# MaTouch_ESP32-S3_7_5_Eink_AI_Mic_Array_V.net
KiCad netlist of a schematic drawn in EAGLE
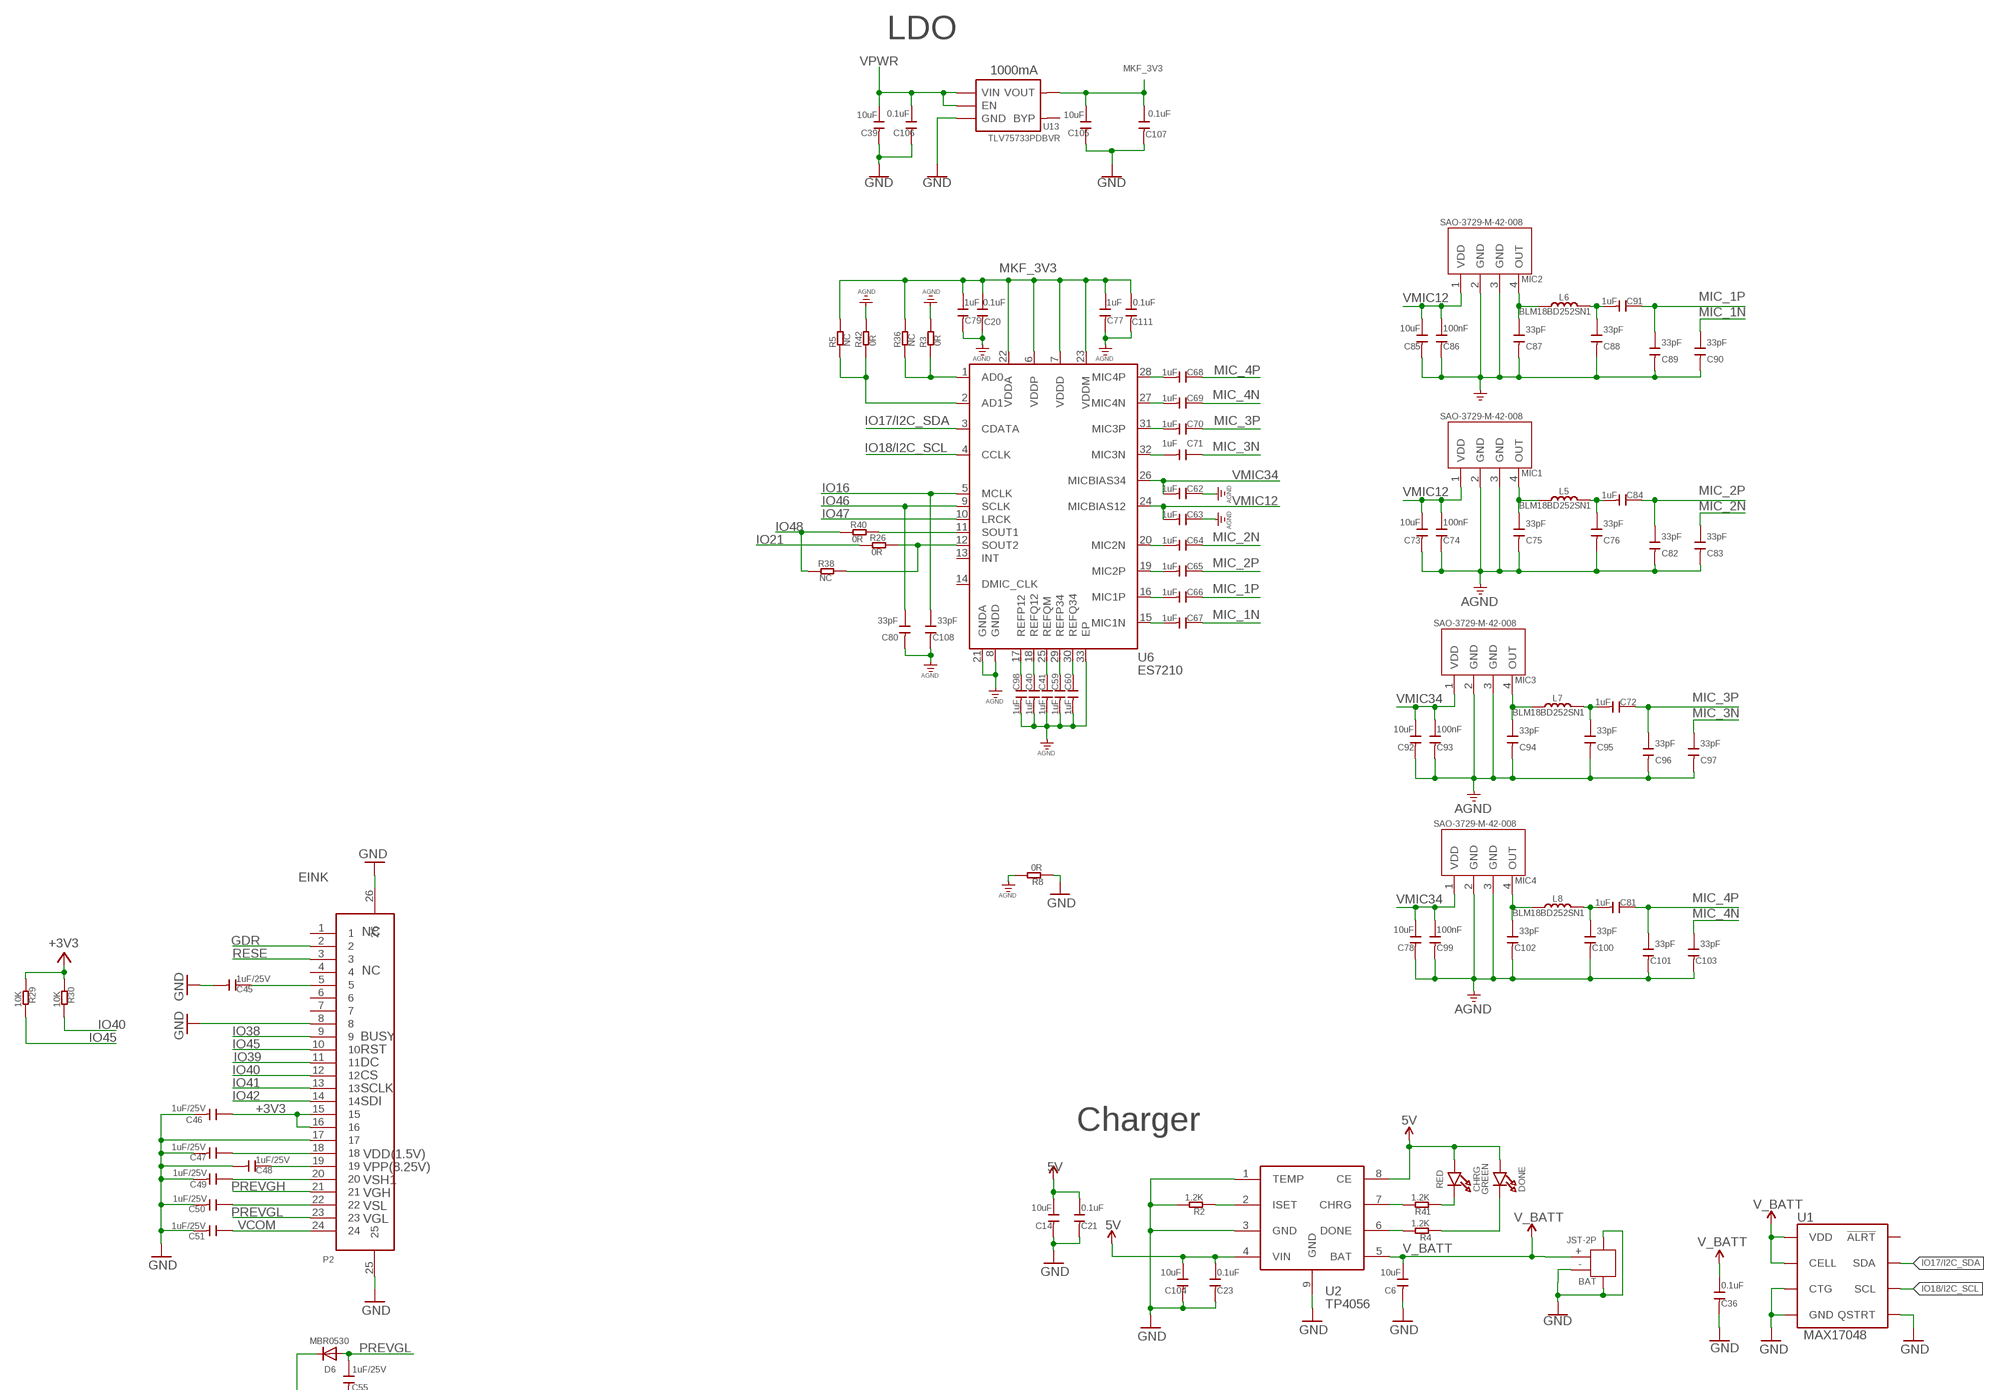
[diagram p0: schematic, sheet 1, part 1 of 3]
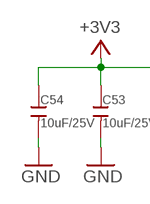
[diagram p1: schematic, sheet 1, part 2 of 3]
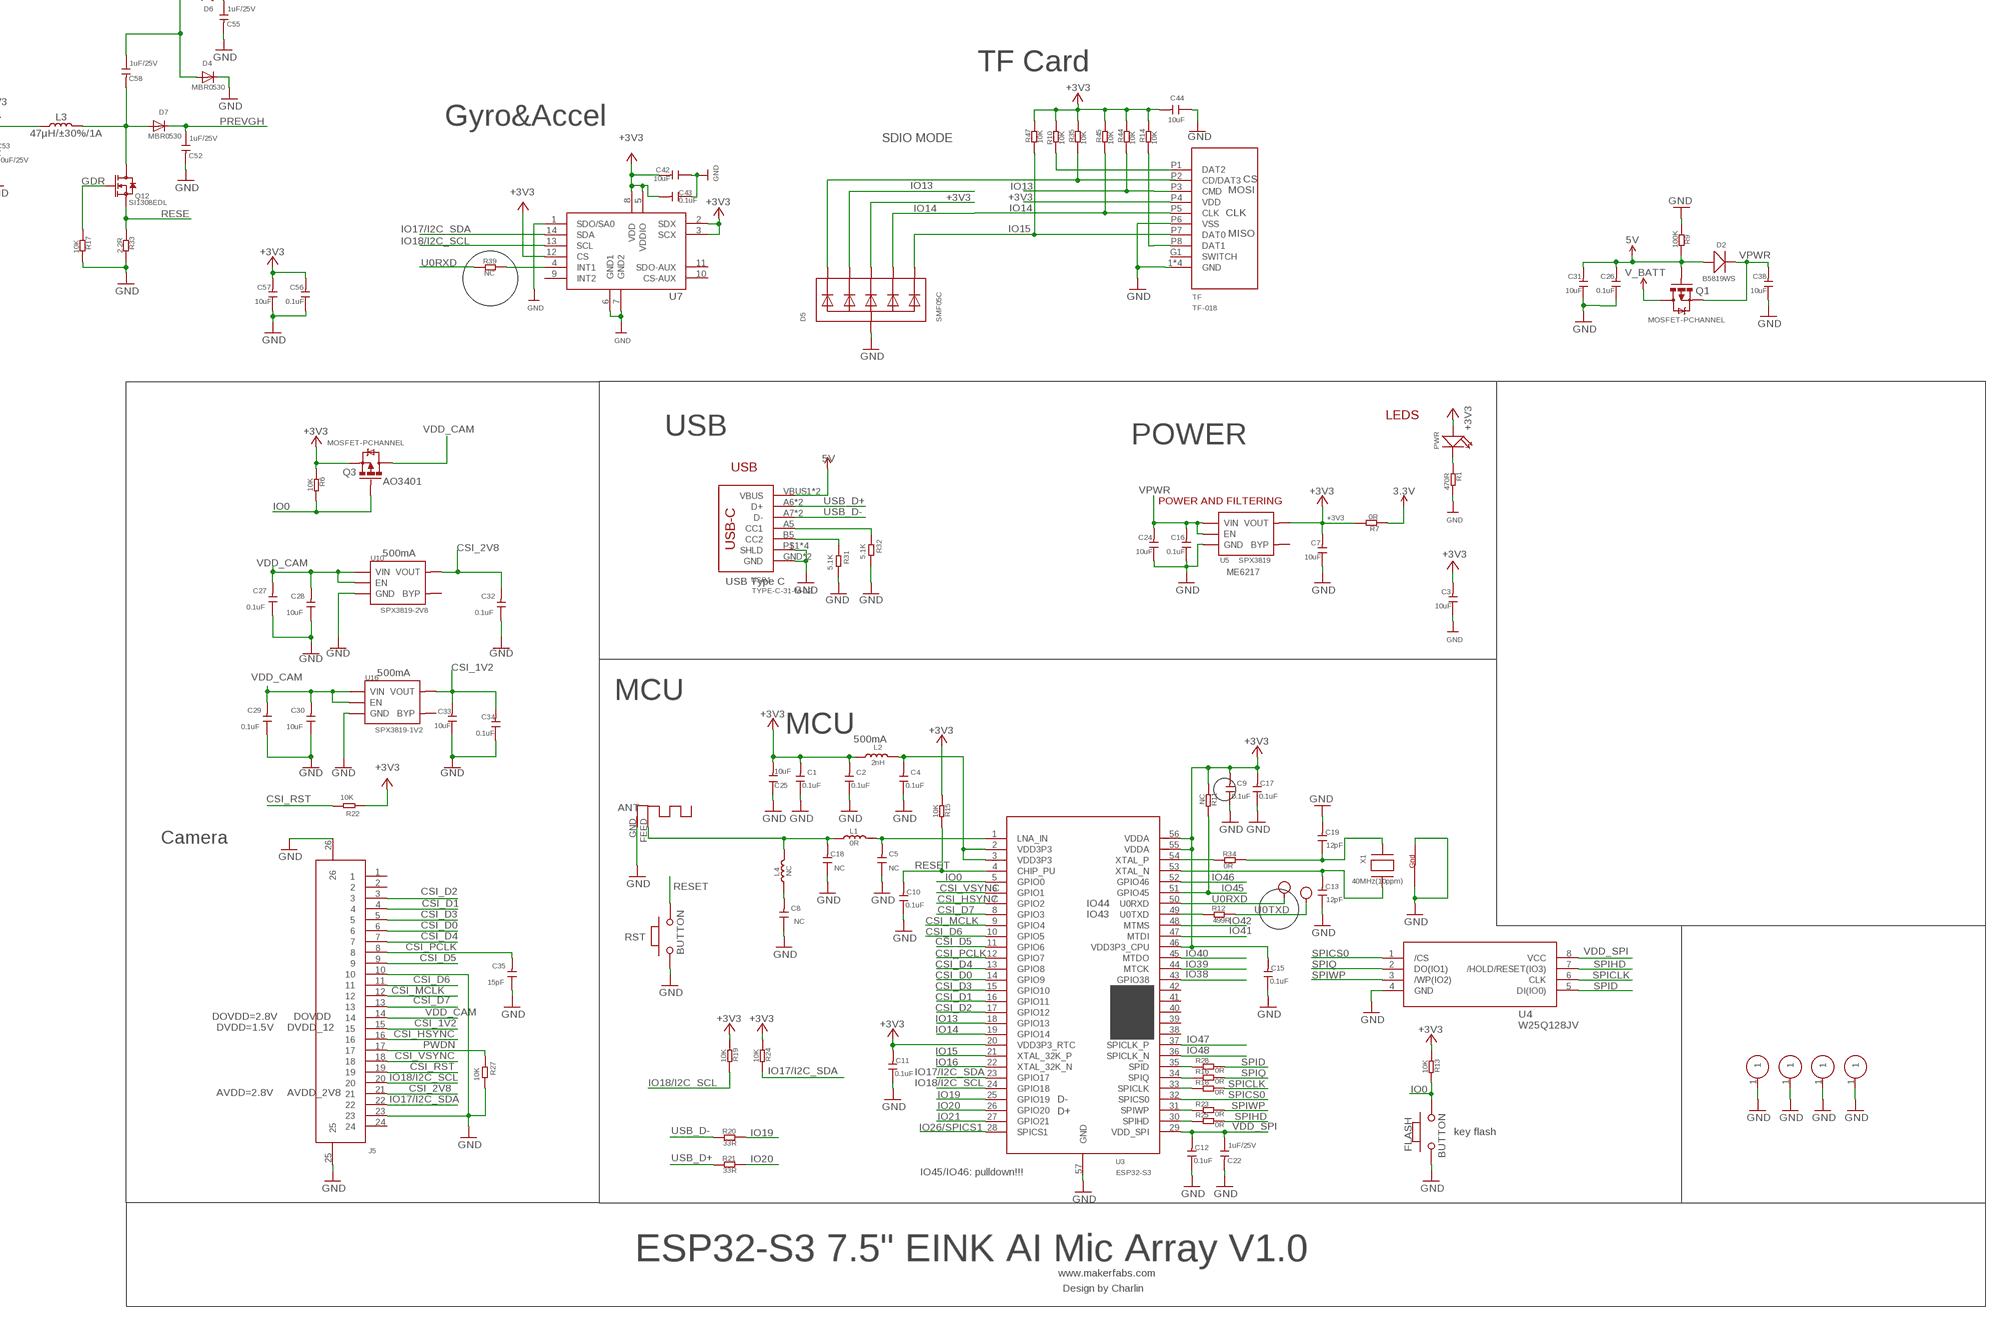
[diagram p2: schematic, sheet 1, part 3 of 3]

(export (version "E")
  (design (tool "Eeschema 10.0.6"))
  (components
    (comp (ref "ANT1")
      (value "ANTENNA")
      (footprint "eagle-import:RN-ANT")
      (libsource (lib "eagle-import") (part "ANTENNA"))
    )
    (comp (ref "BAT")
      (value "JST-2P")
      (footprint "eagle-import:HW2-SMD-2.0-90D")
      (libsource (lib "eagle-import") (part "JST-2P-SMD'2.0'"))
    )
    (comp (ref "C1")
      (value "0.1uF")
      (footprint "eagle-import:DISCRETE_C0402")
      (libsource (lib "eagle-import") (part "DISCRETE_C-0402"))
    )
    (comp (ref "C2")
      (value "0.1uF")
      (footprint "eagle-import:DISCRETE_C0402")
      (libsource (lib "eagle-import") (part "DISCRETE_C-0402"))
    )
    (comp (ref "C3")
      (value "10uF")
      (footprint "eagle-import:DISCRETE_C0402")
      (libsource (lib "eagle-import") (part "DISCRETE_C-0402"))
    )
    (comp (ref "C4")
      (value "0.1uF")
      (footprint "eagle-import:DISCRETE_C0402")
      (libsource (lib "eagle-import") (part "DISCRETE_C-0402"))
    )
    (comp (ref "C5")
      (value "NC")
      (footprint "eagle-import:DISCRETE_C0402")
      (libsource (lib "eagle-import") (part "DISCRETE_C-0402"))
    )
    (comp (ref "C6")
      (value "10uF")
      (footprint "eagle-import:DISCRETE_C0402")
      (libsource (lib "eagle-import") (part "DISCRETE_C-0402"))
    )
    (comp (ref "C7")
      (value "10uF")
      (footprint "eagle-import:DISCRETE_C0402")
      (libsource (lib "eagle-import") (part "DISCRETE_C-0402"))
    )
    (comp (ref "C8")
      (value "NC")
      (footprint "eagle-import:DISCRETE_C0402")
      (libsource (lib "eagle-import") (part "DISCRETE_C-0402"))
    )
    (comp (ref "C9")
      (value "0.1uF")
      (footprint "eagle-import:DISCRETE_C0402")
      (libsource (lib "eagle-import") (part "DISCRETE_C-0402"))
    )
    (comp (ref "C10")
      (value "0.1uF")
      (footprint "eagle-import:DISCRETE_C0402")
      (libsource (lib "eagle-import") (part "DISCRETE_C-0402"))
    )
    (comp (ref "C11")
      (value "0.1uF")
      (footprint "eagle-import:DISCRETE_C0402")
      (libsource (lib "eagle-import") (part "DISCRETE_C-0402"))
    )
    (comp (ref "C12")
      (value "0.1uF")
      (footprint "eagle-import:DISCRETE_C0402")
      (libsource (lib "eagle-import") (part "DISCRETE_C-0402"))
    )
    (comp (ref "C13")
      (value "12pF")
      (footprint "eagle-import:DISCRETE_C0402")
      (libsource (lib "eagle-import") (part "DISCRETE_C-0402"))
    )
    (comp (ref "C14")
      (value "10uF")
      (footprint "eagle-import:DISCRETE_C0402")
      (libsource (lib "eagle-import") (part "DISCRETE_C-0402"))
    )
    (comp (ref "C15")
      (value "0.1uF")
      (footprint "eagle-import:DISCRETE_C0402")
      (libsource (lib "eagle-import") (part "DISCRETE_C-0402"))
    )
    (comp (ref "C16")
      (value "0.1uF")
      (footprint "eagle-import:DISCRETE_C0402")
      (libsource (lib "eagle-import") (part "DISCRETE_C-0402"))
    )
    (comp (ref "C17")
      (value "0.1uF")
      (footprint "eagle-import:DISCRETE_C0402")
      (libsource (lib "eagle-import") (part "DISCRETE_C-0402"))
    )
    (comp (ref "C18")
      (value "NC")
      (footprint "eagle-import:DISCRETE_C0402")
      (libsource (lib "eagle-import") (part "DISCRETE_C-0402"))
    )
    (comp (ref "C19")
      (value "12pF")
      (footprint "eagle-import:DISCRETE_C0402")
      (libsource (lib "eagle-import") (part "DISCRETE_C-0402"))
    )
    (comp (ref "C20")
      (value "0.1uF")
      (footprint "eagle-import:DISCRETE_C0402")
      (libsource (lib "eagle-import") (part "DISCRETE_C-0402"))
    )
    (comp (ref "C21")
      (value "0.1uF")
      (footprint "eagle-import:DISCRETE_C0402")
      (libsource (lib "eagle-import") (part "DISCRETE_C-0402"))
    )
    (comp (ref "C22")
      (value "1uF/25V")
      (footprint "eagle-import:DISCRETE_C0402")
      (libsource (lib "eagle-import") (part "DISCRETE_C-0402"))
    )
    (comp (ref "C23")
      (value "0.1uF")
      (footprint "eagle-import:DISCRETE_C0402")
      (libsource (lib "eagle-import") (part "DISCRETE_C-0402"))
    )
    (comp (ref "C24")
      (value "10uF")
      (footprint "eagle-import:DISCRETE_C0402")
      (libsource (lib "eagle-import") (part "DISCRETE_C-0402"))
    )
    (comp (ref "C25")
      (value "10uF")
      (footprint "eagle-import:DISCRETE_C0603")
      (libsource (lib "eagle-import") (part "DISCRETE_C-0603"))
    )
    (comp (ref "C26")
      (value "0.1uF")
      (footprint "eagle-import:DISCRETE_C0402")
      (libsource (lib "eagle-import") (part "DISCRETE_C-0402"))
    )
    (comp (ref "C27")
      (value "0.1uF")
      (footprint "eagle-import:DISCRETE_C0402")
      (libsource (lib "eagle-import") (part "DISCRETE_C-0402"))
    )
    (comp (ref "C28")
      (value "10uF")
      (footprint "eagle-import:DISCRETE_C0402")
      (libsource (lib "eagle-import") (part "DISCRETE_C-0402"))
    )
    (comp (ref "C29")
      (value "0.1uF")
      (footprint "eagle-import:DISCRETE_C0402")
      (libsource (lib "eagle-import") (part "DISCRETE_C-0402"))
    )
    (comp (ref "C30")
      (value "10uF")
      (footprint "eagle-import:DISCRETE_C0402")
      (libsource (lib "eagle-import") (part "DISCRETE_C-0402"))
    )
    (comp (ref "C31")
      (value "10uF")
      (footprint "eagle-import:DISCRETE_C0402")
      (libsource (lib "eagle-import") (part "DISCRETE_C-0402"))
    )
    (comp (ref "C32")
      (value "0.1uF")
      (footprint "eagle-import:DISCRETE_C0402")
      (libsource (lib "eagle-import") (part "DISCRETE_C-0402"))
    )
    (comp (ref "C33")
      (value "10uF")
      (footprint "eagle-import:DISCRETE_C0402")
      (libsource (lib "eagle-import") (part "DISCRETE_C-0402"))
    )
    (comp (ref "C34")
      (value "0.1uF")
      (footprint "eagle-import:DISCRETE_C0402")
      (libsource (lib "eagle-import") (part "DISCRETE_C-0402"))
    )
    (comp (ref "C35")
      (value "15pF")
      (footprint "eagle-import:DISCRETE_C0402")
      (libsource (lib "eagle-import") (part "DISCRETE_C-0402"))
    )
    (comp (ref "C36")
      (value "0.1uF")
      (footprint "eagle-import:DISCRETE_C0402")
      (libsource (lib "eagle-import") (part "DISCRETE_C-0402"))
    )
    (comp (ref "C38")
      (value "10uF")
      (footprint "eagle-import:DISCRETE_C0402")
      (libsource (lib "eagle-import") (part "DISCRETE_C-0402"))
    )
    (comp (ref "C39")
      (value "10uF")
      (footprint "eagle-import:DISCRETE_C0402")
      (libsource (lib "eagle-import") (part "DISCRETE_C-0402"))
    )
    (comp (ref "C40")
      (value "1uF")
      (footprint "eagle-import:DISCRETE_C0402")
      (libsource (lib "eagle-import") (part "DISCRETE_C-0402"))
    )
    (comp (ref "C41")
      (value "1uF")
      (footprint "eagle-import:DISCRETE_C0402")
      (libsource (lib "eagle-import") (part "DISCRETE_C-0402"))
    )
    (comp (ref "C42")
      (value "10uF")
      (footprint "eagle-import:DISCRETE_C0402")
      (libsource (lib "eagle-import") (part "DISCRETE_C-0402"))
    )
    (comp (ref "C43")
      (value "0.1uF")
      (footprint "eagle-import:DISCRETE_C0402")
      (libsource (lib "eagle-import") (part "DISCRETE_C-0402"))
    )
    (comp (ref "C44")
      (value "10uF")
      (footprint "eagle-import:DISCRETE_C0402")
      (libsource (lib "eagle-import") (part "DISCRETE_C-0402"))
    )
    (comp (ref "C45")
      (value "1uF/25V")
      (footprint "eagle-import:DISCRETE_C0402")
      (libsource (lib "eagle-import") (part "DISCRETE_C-0402"))
    )
    (comp (ref "C46")
      (value "1uF/25V")
      (footprint "eagle-import:DISCRETE_C0402")
      (libsource (lib "eagle-import") (part "DISCRETE_C-0402"))
    )
    (comp (ref "C47")
      (value "1uF/25V")
      (footprint "eagle-import:DISCRETE_C0402")
      (libsource (lib "eagle-import") (part "DISCRETE_C-0402"))
    )
    (comp (ref "C48")
      (value "1uF/25V")
      (footprint "eagle-import:DISCRETE_C0402")
      (libsource (lib "eagle-import") (part "DISCRETE_C-0402"))
    )
    (comp (ref "C49")
      (value "1uF/25V")
      (footprint "eagle-import:DISCRETE_C0402")
      (libsource (lib "eagle-import") (part "DISCRETE_C-0402"))
    )
    (comp (ref "C50")
      (value "1uF/25V")
      (footprint "eagle-import:DISCRETE_C0402")
      (libsource (lib "eagle-import") (part "DISCRETE_C-0402"))
    )
    (comp (ref "C51")
      (value "1uF/25V")
      (footprint "eagle-import:DISCRETE_C0402")
      (libsource (lib "eagle-import") (part "DISCRETE_C-0402"))
    )
    (comp (ref "C52")
      (value "1uF/25V")
      (footprint "eagle-import:DISCRETE_C0402")
      (libsource (lib "eagle-import") (part "DISCRETE_C-0402"))
    )
    (comp (ref "C53")
      (value "10uF/25V")
      (footprint "eagle-import:C0603")
      (libsource (lib "eagle-import") (part "C-0603"))
    )
    (comp (ref "C54")
      (value "10uF/25V")
      (footprint "eagle-import:C0603")
      (libsource (lib "eagle-import") (part "C-0603"))
    )
    (comp (ref "C55")
      (value "1uF/25V")
      (footprint "eagle-import:DISCRETE_C0402")
      (libsource (lib "eagle-import") (part "DISCRETE_C-0402"))
    )
    (comp (ref "C56")
      (value "0.1uF")
      (footprint "eagle-import:DISCRETE_C0402")
      (libsource (lib "eagle-import") (part "DISCRETE_C-0402"))
    )
    (comp (ref "C57")
      (value "10uF")
      (footprint "eagle-import:DISCRETE_C0402")
      (libsource (lib "eagle-import") (part "DISCRETE_C-0402"))
    )
    (comp (ref "C58")
      (value "1uF/25V")
      (footprint "eagle-import:DISCRETE_C0402")
      (libsource (lib "eagle-import") (part "DISCRETE_C-0402"))
    )
    (comp (ref "C59")
      (value "1uF")
      (footprint "eagle-import:DISCRETE_C0402")
      (libsource (lib "eagle-import") (part "DISCRETE_C-0402"))
    )
    (comp (ref "C60")
      (value "1uF")
      (footprint "eagle-import:DISCRETE_C0402")
      (libsource (lib "eagle-import") (part "DISCRETE_C-0402"))
    )
    (comp (ref "C62")
      (value "1uF")
      (footprint "eagle-import:DISCRETE_C0402")
      (libsource (lib "eagle-import") (part "DISCRETE_C-0402"))
    )
    (comp (ref "C63")
      (value "1uF")
      (footprint "eagle-import:DISCRETE_C0402")
      (libsource (lib "eagle-import") (part "DISCRETE_C-0402"))
    )
    (comp (ref "C64")
      (value "1uF")
      (footprint "eagle-import:DISCRETE_C0402")
      (libsource (lib "eagle-import") (part "DISCRETE_C-0402"))
    )
    (comp (ref "C65")
      (value "1uF")
      (footprint "eagle-import:DISCRETE_C0402")
      (libsource (lib "eagle-import") (part "DISCRETE_C-0402"))
    )
    (comp (ref "C66")
      (value "1uF")
      (footprint "eagle-import:DISCRETE_C0402")
      (libsource (lib "eagle-import") (part "DISCRETE_C-0402"))
    )
    (comp (ref "C67")
      (value "1uF")
      (footprint "eagle-import:DISCRETE_C0402")
      (libsource (lib "eagle-import") (part "DISCRETE_C-0402"))
    )
    (comp (ref "C68")
      (value "1uF")
      (footprint "eagle-import:DISCRETE_C0402")
      (libsource (lib "eagle-import") (part "DISCRETE_C-0402"))
    )
    (comp (ref "C69")
      (value "1uF")
      (footprint "eagle-import:DISCRETE_C0402")
      (libsource (lib "eagle-import") (part "DISCRETE_C-0402"))
    )
    (comp (ref "C70")
      (value "1uF")
      (footprint "eagle-import:DISCRETE_C0402")
      (libsource (lib "eagle-import") (part "DISCRETE_C-0402"))
    )
    (comp (ref "C71")
      (value "1uF")
      (footprint "eagle-import:DISCRETE_C0402")
      (libsource (lib "eagle-import") (part "DISCRETE_C-0402"))
    )
    (comp (ref "C72")
      (value "1uF")
      (footprint "eagle-import:DISCRETE_C0402")
      (libsource (lib "eagle-import") (part "DISCRETE_C-0402"))
    )
    (comp (ref "C73")
      (value "10uF")
      (footprint "eagle-import:DISCRETE_C0402")
      (libsource (lib "eagle-import") (part "DISCRETE_C-0402"))
    )
    (comp (ref "C74")
      (value "100nF")
      (footprint "eagle-import:DISCRETE_C0402")
      (libsource (lib "eagle-import") (part "DISCRETE_C-0402"))
    )
    (comp (ref "C75")
      (value "33pF")
      (footprint "eagle-import:DISCRETE_C0402")
      (libsource (lib "eagle-import") (part "DISCRETE_C-0402"))
    )
    (comp (ref "C76")
      (value "33pF")
      (footprint "eagle-import:DISCRETE_C0402")
      (libsource (lib "eagle-import") (part "DISCRETE_C-0402"))
    )
    (comp (ref "C77")
      (value "1uF")
      (footprint "eagle-import:DISCRETE_C0402")
      (libsource (lib "eagle-import") (part "DISCRETE_C-0402"))
    )
    (comp (ref "C78")
      (value "10uF")
      (footprint "eagle-import:DISCRETE_C0402")
      (libsource (lib "eagle-import") (part "DISCRETE_C-0402"))
    )
    (comp (ref "C79")
      (value "1uF")
      (footprint "eagle-import:DISCRETE_C0402")
      (libsource (lib "eagle-import") (part "DISCRETE_C-0402"))
    )
    (comp (ref "C80")
      (value "33pF")
      (footprint "eagle-import:DISCRETE_C0402")
      (libsource (lib "eagle-import") (part "DISCRETE_C-0402"))
    )
    (comp (ref "C81")
      (value "1uF")
      (footprint "eagle-import:DISCRETE_C0402")
      (libsource (lib "eagle-import") (part "DISCRETE_C-0402"))
    )
    (comp (ref "C82")
      (value "33pF")
      (footprint "eagle-import:DISCRETE_C0402")
      (libsource (lib "eagle-import") (part "DISCRETE_C-0402"))
    )
    (comp (ref "C83")
      (value "33pF")
      (footprint "eagle-import:DISCRETE_C0402")
      (libsource (lib "eagle-import") (part "DISCRETE_C-0402"))
    )
    (comp (ref "C84")
      (value "1uF")
      (footprint "eagle-import:DISCRETE_C0402")
      (libsource (lib "eagle-import") (part "DISCRETE_C-0402"))
    )
    (comp (ref "C85")
      (value "10uF")
      (footprint "eagle-import:DISCRETE_C0402")
      (libsource (lib "eagle-import") (part "DISCRETE_C-0402"))
    )
    (comp (ref "C86")
      (value "100nF")
      (footprint "eagle-import:DISCRETE_C0402")
      (libsource (lib "eagle-import") (part "DISCRETE_C-0402"))
    )
    (comp (ref "C87")
      (value "33pF")
      (footprint "eagle-import:DISCRETE_C0402")
      (libsource (lib "eagle-import") (part "DISCRETE_C-0402"))
    )
    (comp (ref "C88")
      (value "33pF")
      (footprint "eagle-import:DISCRETE_C0402")
      (libsource (lib "eagle-import") (part "DISCRETE_C-0402"))
    )
    (comp (ref "C89")
      (value "33pF")
      (footprint "eagle-import:DISCRETE_C0402")
      (libsource (lib "eagle-import") (part "DISCRETE_C-0402"))
    )
    (comp (ref "C90")
      (value "33pF")
      (footprint "eagle-import:DISCRETE_C0402")
      (libsource (lib "eagle-import") (part "DISCRETE_C-0402"))
    )
    (comp (ref "C91")
      (value "1uF")
      (footprint "eagle-import:DISCRETE_C0402")
      (libsource (lib "eagle-import") (part "DISCRETE_C-0402"))
    )
    (comp (ref "C92")
      (value "10uF")
      (footprint "eagle-import:DISCRETE_C0402")
      (libsource (lib "eagle-import") (part "DISCRETE_C-0402"))
    )
    (comp (ref "C93")
      (value "100nF")
      (footprint "eagle-import:DISCRETE_C0402")
      (libsource (lib "eagle-import") (part "DISCRETE_C-0402"))
    )
    (comp (ref "C94")
      (value "33pF")
      (footprint "eagle-import:DISCRETE_C0402")
      (libsource (lib "eagle-import") (part "DISCRETE_C-0402"))
    )
    (comp (ref "C95")
      (value "33pF")
      (footprint "eagle-import:DISCRETE_C0402")
      (libsource (lib "eagle-import") (part "DISCRETE_C-0402"))
    )
    (comp (ref "C96")
      (value "33pF")
      (footprint "eagle-import:DISCRETE_C0402")
      (libsource (lib "eagle-import") (part "DISCRETE_C-0402"))
    )
    (comp (ref "C97")
      (value "33pF")
      (footprint "eagle-import:DISCRETE_C0402")
      (libsource (lib "eagle-import") (part "DISCRETE_C-0402"))
    )
    (comp (ref "C98")
      (value "1uF")
      (footprint "eagle-import:DISCRETE_C0402")
      (libsource (lib "eagle-import") (part "DISCRETE_C-0402"))
    )
    (comp (ref "C99")
      (value "100nF")
      (footprint "eagle-import:DISCRETE_C0402")
      (libsource (lib "eagle-import") (part "DISCRETE_C-0402"))
    )
    (comp (ref "C100")
      (value "33pF")
      (footprint "eagle-import:DISCRETE_C0402")
      (libsource (lib "eagle-import") (part "DISCRETE_C-0402"))
    )
    (comp (ref "C101")
      (value "33pF")
      (footprint "eagle-import:DISCRETE_C0402")
      (libsource (lib "eagle-import") (part "DISCRETE_C-0402"))
    )
    (comp (ref "C102")
      (value "33pF")
      (footprint "eagle-import:DISCRETE_C0402")
      (libsource (lib "eagle-import") (part "DISCRETE_C-0402"))
    )
    (comp (ref "C103")
      (value "33pF")
      (footprint "eagle-import:DISCRETE_C0402")
      (libsource (lib "eagle-import") (part "DISCRETE_C-0402"))
    )
    (comp (ref "C104")
      (value "10uF")
      (footprint "eagle-import:DISCRETE_C0402")
      (libsource (lib "eagle-import") (part "DISCRETE_C-0402"))
    )
    (comp (ref "C105")
      (value "10uF")
      (footprint "eagle-import:DISCRETE_C0402")
      (libsource (lib "eagle-import") (part "DISCRETE_C-0402"))
    )
    (comp (ref "C106")
      (value "0.1uF")
      (footprint "eagle-import:DISCRETE_C0402")
      (libsource (lib "eagle-import") (part "DISCRETE_C-0402"))
    )
    (comp (ref "C107")
      (value "0.1uF")
      (footprint "eagle-import:DISCRETE_C0402")
      (libsource (lib "eagle-import") (part "DISCRETE_C-0402"))
    )
    (comp (ref "C108")
      (value "33pF")
      (footprint "eagle-import:DISCRETE_C0402")
      (libsource (lib "eagle-import") (part "DISCRETE_C-0402"))
    )
    (comp (ref "C111")
      (value "0.1uF")
      (footprint "eagle-import:DISCRETE_C0402")
      (libsource (lib "eagle-import") (part "DISCRETE_C-0402"))
    )
    (comp (ref "CHRG")
      (value "RED")
      (footprint "eagle-import:CHIPLED_0805_NOOUTLINE")
      (libsource (lib "eagle-import") (part "LED0805_NOOUTLINE"))
    )
    (comp (ref "D2")
      (value "B5819WS")
      (footprint "eagle-import:SOD323")
      (libsource (lib "eagle-import") (part "D'0805'"))
    )
    (comp (ref "D4")
      (value "MBR0530")
      (footprint "eagle-import:SOD-323F")
      (libsource (lib "eagle-import") (part "DIODESOD-323F"))
    )
    (comp (ref "D5")
      (value "SMF05C")
      (footprint "eagle-import:SOT363")
      (libsource (lib "eagle-import") (part "TVSARRAY_5LANE"))
    )
    (comp (ref "D6")
      (value "MBR0530")
      (footprint "eagle-import:SOD-323F")
      (libsource (lib "eagle-import") (part "DIODESOD-323F"))
    )
    (comp (ref "D7")
      (value "MBR0530")
      (footprint "eagle-import:SOD-323F")
      (libsource (lib "eagle-import") (part "DIODESOD-323F"))
    )
    (comp (ref "DONE")
      (value "GREEN")
      (footprint "eagle-import:CHIPLED_0805_NOOUTLINE")
      (libsource (lib "eagle-import") (part "LED0805_NOOUTLINE"))
    )
    (comp (ref "FLASH")
      (value "BUTTON")
      (footprint "eagle-import:157SW")
      (libsource (lib "eagle-import") (part "PB157"))
    )
    (comp (ref "J5")
      (value "FPC-24P")
      (footprint "eagle-import:SMD26-50P-1760L450W")
      (libsource (lib "eagle-import") (part "FPC-24P"))
    )
    (comp (ref "L1")
      (value "0R")
      (footprint "eagle-import:DISCRETE_L0402")
      (libsource (lib "eagle-import") (part "DISCRETE_L0402"))
    )
    (comp (ref "L2")
      (value "2nH")
      (footprint "eagle-import:DISCRETE_L0603")
      (libsource (lib "eagle-import") (part "DISCRETE_L0603"))
    )
    (comp (ref "L3")
      (value "47µH/±30%/1A")
      (footprint "eagle-import:CR54")
      (fields (field (name "PROD_ID") "NDUC-10789"))
      (libsource (lib "eagle-import") (part "INDUCTOR-CR54-47UH"))
    )
    (comp (ref "L4")
      (value "NC")
      (footprint "eagle-import:DISCRETE_L0402")
      (libsource (lib "eagle-import") (part "DISCRETE_L0402"))
    )
    (comp (ref "L5")
      (value "BLM18BD252SN1")
      (footprint "eagle-import:L0603")
      (libsource (lib "eagle-import") (part "INDUCTOR/FERRITE-BEAD'0603'"))
    )
    (comp (ref "L6")
      (value "BLM18BD252SN1")
      (footprint "eagle-import:L0603")
      (libsource (lib "eagle-import") (part "INDUCTOR/FERRITE-BEAD'0603'"))
    )
    (comp (ref "L7")
      (value "BLM18BD252SN1")
      (footprint "eagle-import:L0603")
      (libsource (lib "eagle-import") (part "INDUCTOR/FERRITE-BEAD'0603'"))
    )
    (comp (ref "L8")
      (value "BLM18BD252SN1")
      (footprint "eagle-import:L0603")
      (libsource (lib "eagle-import") (part "INDUCTOR/FERRITE-BEAD'0603'"))
    )
    (comp (ref "MIC1")
      (value "SAO-3729-M-42-008")
      (footprint "eagle-import:MIC4-SMD-3.76X2.95MM")
      (libsource (lib "eagle-import") (part "MIC-MSM421A3729H8-C"))
    )
    (comp (ref "MIC2")
      (value "SAO-3729-M-42-008")
      (footprint "eagle-import:MIC4-SMD-3.76X2.95MM")
      (libsource (lib "eagle-import") (part "MIC-MSM421A3729H8-C"))
    )
    (comp (ref "MIC3")
      (value "SAO-3729-M-42-008")
      (footprint "eagle-import:MIC4-SMD-3.76X2.95MM")
      (libsource (lib "eagle-import") (part "MIC-MSM421A3729H8-C"))
    )
    (comp (ref "MIC4")
      (value "SAO-3729-M-42-008")
      (footprint "eagle-import:MIC4-SMD-3.76X2.95MM")
      (libsource (lib "eagle-import") (part "MIC-MSM421A3729H8-C"))
    )
    (comp (ref "P2")
      (value "FPC-24P")
      (footprint "eagle-import:SMD26-50P-1760L450W")
      (libsource (lib "eagle-import") (part "FPC-24P"))
    )
    (comp (ref "PWR")
      (value "DISCRETE_LED0603")
      (footprint "eagle-import:DISCRETE_LED-0603")
      (libsource (lib "eagle-import") (part "DISCRETE_LED0603"))
    )
    (comp (ref "Q1")
      (value "MOSFET-PCHANNEL")
      (footprint "eagle-import:SOT23-3")
      (libsource (lib "eagle-import") (part "MOSFET-PCHANNEL"))
    )
    (comp (ref "Q3")
      (value "MOSFET-PCHANNEL")
      (footprint "eagle-import:SOT23-3")
      (libsource (lib "eagle-import") (part "MOSFET-PCHANNEL"))
    )
    (comp (ref "Q12")
      (value "SI1308EDL")
      (footprint "eagle-import:SOT23")
      (libsource (lib "eagle-import") (part "MOSFET-N'SOT23'"))
    )
    (comp (ref "R1")
      (value "470R")
      (footprint "eagle-import:DISCRETE_R0402")
      (libsource (lib "eagle-import") (part "DISCRETE_R-0402"))
    )
    (comp (ref "R2")
      (value "1.2K")
      (footprint "eagle-import:DISCRETE_R0402")
      (libsource (lib "eagle-import") (part "DISCRETE_R-0402"))
    )
    (comp (ref "R3")
      (value "0R")
      (footprint "eagle-import:DISCRETE_R0402")
      (libsource (lib "eagle-import") (part "DISCRETE_R-0402"))
    )
    (comp (ref "R4")
      (value "1.2K")
      (footprint "eagle-import:DISCRETE_R0402")
      (libsource (lib "eagle-import") (part "DISCRETE_R-0402"))
    )
    (comp (ref "R5")
      (value "NC")
      (footprint "eagle-import:DISCRETE_R0402")
      (libsource (lib "eagle-import") (part "DISCRETE_R-0402"))
    )
    (comp (ref "R6")
      (value "10K")
      (footprint "eagle-import:DISCRETE_R0402")
      (libsource (lib "eagle-import") (part "DISCRETE_R-0402"))
    )
    (comp (ref "R7")
      (value "0R")
      (footprint "eagle-import:DISCRETE_R0402")
      (libsource (lib "eagle-import") (part "DISCRETE_R-0402"))
    )
    (comp (ref "R8")
      (value "0R")
      (footprint "eagle-import:DISCRETE_R0402")
      (libsource (lib "eagle-import") (part "DISCRETE_R-0402"))
    )
    (comp (ref "R9")
      (value "100K")
      (footprint "eagle-import:DISCRETE_R0402")
      (libsource (lib "eagle-import") (part "DISCRETE_R-0402"))
    )
    (comp (ref "R10")
      (value "10K")
      (footprint "eagle-import:DISCRETE_R0402")
      (libsource (lib "eagle-import") (part "DISCRETE_R-0402"))
    )
    (comp (ref "R11")
      (value "NC")
      (footprint "eagle-import:DISCRETE_R0402")
      (libsource (lib "eagle-import") (part "DISCRETE_R-0402"))
    )
    (comp (ref "R12")
      (value "499R")
      (footprint "eagle-import:DISCRETE_R0402")
      (libsource (lib "eagle-import") (part "DISCRETE_R-0402"))
    )
    (comp (ref "R13")
      (value "10K")
      (footprint "eagle-import:DISCRETE_R0402")
      (libsource (lib "eagle-import") (part "DISCRETE_R-0402"))
    )
    (comp (ref "R14")
      (value "10K")
      (footprint "eagle-import:DISCRETE_R0402")
      (libsource (lib "eagle-import") (part "DISCRETE_R-0402"))
    )
    (comp (ref "R15")
      (value "10K")
      (footprint "eagle-import:DISCRETE_R0402")
      (libsource (lib "eagle-import") (part "DISCRETE_R-0402"))
    )
    (comp (ref "R16")
      (value "0R")
      (footprint "eagle-import:DISCRETE_R0402")
      (libsource (lib "eagle-import") (part "DISCRETE_R-0402"))
    )
    (comp (ref "R17")
      (value "10K")
      (footprint "eagle-import:DISCRETE_R0402")
      (libsource (lib "eagle-import") (part "DISCRETE_R-0402"))
    )
    (comp (ref "R18")
      (value "0R")
      (footprint "eagle-import:DISCRETE_R0402")
      (libsource (lib "eagle-import") (part "DISCRETE_R-0402"))
    )
    (comp (ref "R19")
      (value "10K")
      (footprint "eagle-import:DISCRETE_R0402")
      (libsource (lib "eagle-import") (part "DISCRETE_R-0402"))
    )
    (comp (ref "R20")
      (value "33R")
      (footprint "eagle-import:DISCRETE_R0402")
      (libsource (lib "eagle-import") (part "DISCRETE_R-0402"))
    )
    (comp (ref "R21")
      (value "33R")
      (footprint "eagle-import:DISCRETE_R0402")
      (libsource (lib "eagle-import") (part "DISCRETE_R-0402"))
    )
    (comp (ref "R22")
      (value "10K")
      (footprint "eagle-import:DISCRETE_R0402")
      (libsource (lib "eagle-import") (part "DISCRETE_R-0402"))
    )
    (comp (ref "R23")
      (value "0R")
      (footprint "eagle-import:DISCRETE_R0402")
      (libsource (lib "eagle-import") (part "DISCRETE_R-0402"))
    )
    (comp (ref "R24")
      (value "10K")
      (footprint "eagle-import:DISCRETE_R0402")
      (libsource (lib "eagle-import") (part "DISCRETE_R-0402"))
    )
    (comp (ref "R25")
      (value "0R")
      (footprint "eagle-import:DISCRETE_R0402")
      (libsource (lib "eagle-import") (part "DISCRETE_R-0402"))
    )
    (comp (ref "R26")
      (value "0R")
      (footprint "eagle-import:DISCRETE_R0402")
      (libsource (lib "eagle-import") (part "DISCRETE_R-0402"))
    )
    (comp (ref "R27")
      (value "10K")
      (footprint "eagle-import:DISCRETE_R0402")
      (libsource (lib "eagle-import") (part "DISCRETE_R-0402"))
    )
    (comp (ref "R28")
      (value "0R")
      (footprint "eagle-import:DISCRETE_R0402")
      (libsource (lib "eagle-import") (part "DISCRETE_R-0402"))
    )
    (comp (ref "R29")
      (value "10K")
      (footprint "eagle-import:DISCRETE_R0402")
      (libsource (lib "eagle-import") (part "DISCRETE_R-0402"))
    )
    (comp (ref "R30")
      (value "10K")
      (footprint "eagle-import:DISCRETE_R0402")
      (libsource (lib "eagle-import") (part "DISCRETE_R-0402"))
    )
    (comp (ref "R31")
      (value "5.1K")
      (footprint "eagle-import:DISCRETE_R0402")
      (libsource (lib "eagle-import") (part "DISCRETE_R-0402"))
    )
    (comp (ref "R32")
      (value "5.1K")
      (footprint "eagle-import:DISCRETE_R0402")
      (libsource (lib "eagle-import") (part "DISCRETE_R-0402"))
    )
    (comp (ref "R33")
      (value "2.2R")
      (footprint "eagle-import:DISCRETE_R0402")
      (libsource (lib "eagle-import") (part "DISCRETE_R-0402"))
    )
    (comp (ref "R34")
      (value "0R")
      (footprint "eagle-import:DISCRETE_R0402")
      (libsource (lib "eagle-import") (part "DISCRETE_R-0402"))
    )
    (comp (ref "R35")
      (value "10K")
      (footprint "eagle-import:DISCRETE_R0402")
      (libsource (lib "eagle-import") (part "DISCRETE_R-0402"))
    )
    (comp (ref "R36")
      (value "NC")
      (footprint "eagle-import:DISCRETE_R0402")
      (libsource (lib "eagle-import") (part "DISCRETE_R-0402"))
    )
    (comp (ref "R38")
      (value "NC")
      (footprint "eagle-import:DISCRETE_R0402")
      (libsource (lib "eagle-import") (part "DISCRETE_R-0402"))
    )
    (comp (ref "R39")
      (value "NC")
      (footprint "eagle-import:DISCRETE_R0402")
      (libsource (lib "eagle-import") (part "DISCRETE_R-0402"))
    )
    (comp (ref "R40")
      (value "0R")
      (footprint "eagle-import:DISCRETE_R0402")
      (libsource (lib "eagle-import") (part "DISCRETE_R-0402"))
    )
    (comp (ref "R41")
      (value "1.2K")
      (footprint "eagle-import:DISCRETE_R0402")
      (libsource (lib "eagle-import") (part "DISCRETE_R-0402"))
    )
    (comp (ref "R42")
      (value "0R")
      (footprint "eagle-import:DISCRETE_R0402")
      (libsource (lib "eagle-import") (part "DISCRETE_R-0402"))
    )
    (comp (ref "R44")
      (value "10K")
      (footprint "eagle-import:DISCRETE_R0402")
      (libsource (lib "eagle-import") (part "DISCRETE_R-0402"))
    )
    (comp (ref "R45")
      (value "10K")
      (footprint "eagle-import:DISCRETE_R0402")
      (libsource (lib "eagle-import") (part "DISCRETE_R-0402"))
    )
    (comp (ref "R47")
      (value "10K")
      (footprint "eagle-import:DISCRETE_R0402")
      (libsource (lib "eagle-import") (part "DISCRETE_R-0402"))
    )
    (comp (ref "RST")
      (value "BUTTON")
      (footprint "eagle-import:157SW")
      (libsource (lib "eagle-import") (part "PB157"))
    )
    (comp (ref "RX")
      (value "TEST-POINT'4545'")
      (footprint "eagle-import:TP-D45MIL")
      (fields (field (name "PARTNO") "DNP") (field (name "PARTNO_1") "DNP"))
      (libsource (lib "eagle-import") (part "TEST-POINT'4545'"))
    )
    (comp (ref "S1")
      (value "ONEPIN01")
      (footprint "eagle-import:ONEPIN01")
      (libsource (lib "eagle-import") (part "ONEPIN01"))
    )
    (comp (ref "S2")
      (value "ONEPIN01")
      (footprint "eagle-import:ONEPIN01")
      (libsource (lib "eagle-import") (part "ONEPIN01"))
    )
    (comp (ref "S3")
      (value "ONEPIN01")
      (footprint "eagle-import:ONEPIN01")
      (libsource (lib "eagle-import") (part "ONEPIN01"))
    )
    (comp (ref "S4")
      (value "ONEPIN01")
      (footprint "eagle-import:ONEPIN01")
      (libsource (lib "eagle-import") (part "ONEPIN01"))
    )
    (comp (ref "TF")
      (value "TF-018")
      (footprint "eagle-import:TF-018")
      (libsource (lib "eagle-import") (part "TF-018"))
    )
    (comp (ref "TX")
      (value "TEST-POINT'4545'")
      (footprint "eagle-import:TP-D45MIL")
      (fields (field (name "PARTNO") "DNP") (field (name "PARTNO_1") "DNP"))
      (libsource (lib "eagle-import") (part "TEST-POINT'4545'"))
    )
    (comp (ref "U1")
      (value "MAX17048")
      (footprint "eagle-import:DFN-8")
      (libsource (lib "eagle-import") (part "MAX17048DFN8"))
    )
    (comp (ref "U2")
      (value "TP4056")
      (footprint "eagle-import:SOP8-1.27P")
      (libsource (lib "eagle-import") (part "TP4056"))
    )
    (comp (ref "U3")
      (value "ESP32-S3")
      (footprint "eagle-import:QFN56-7_7MM")
      (libsource (lib "eagle-import") (part "ESP32-S3"))
    )
    (comp (ref "U4")
      (value "W25Q128JV")
      (footprint "eagle-import:SOIC-8-208MIL")
      (libsource (lib "eagle-import") (part "W25Q128JV"))
    )
    (comp (ref "U5")
      (value "SPX3819")
      (footprint "eagle-import:SOT23-5")
      (libsource (lib "eagle-import") (part "SPX3819"))
    )
    (comp (ref "U6")
      (value "ES7210")
      (footprint "eagle-import:QFN33-40P400L400W75H-280X280")
      (libsource (lib "eagle-import") (part "ES7210"))
    )
    (comp (ref "U7")
      (value "QMI8658A")
      (footprint "eagle-import:LGA14-50P-300L250W86H")
      (libsource (lib "eagle-import") (part "QMI8658A"))
    )
    (comp (ref "U10")
      (value "SPX3819-2V8")
      (footprint "eagle-import:SOT23-5")
      (libsource (lib "eagle-import") (part "SPX3819"))
    )
    (comp (ref "U13")
      (value "TLV75733PDBVR")
      (footprint "eagle-import:SOT23-5")
      (libsource (lib "eagle-import") (part "SPX3819"))
    )
    (comp (ref "U16")
      (value "SPX3819-1V2")
      (footprint "eagle-import:SOT23-5")
      (libsource (lib "eagle-import") (part "SPX3819"))
    )
    (comp (ref "USB1")
      (value "TYPE-C-31-M-12")
      (footprint "eagle-import:TYPE-C-31-M-12")
      (libsource (lib "eagle-import") (part "TYPE-C-31-M-12"))
    )
    (comp (ref "X1")
      (value "40MHz(10ppm)")
      (footprint "eagle-import:NX3225")
      (libsource (lib "eagle-import") (part "XTAL-4-3225"))
    )
  )
  (nets
    (net (code "1") (name "+3V3") (class "Default")
      (node (ref "C1") (pin "2") (pinfunction "2_2") (pintype "passive"))
      (node (ref "C11") (pin "2") (pinfunction "2_2") (pintype "passive"))
      (node (ref "C15") (pin "2") (pinfunction "2_2") (pintype "passive"))
      (node (ref "C17") (pin "2") (pinfunction "2_2") (pintype "passive"))
      (node (ref "C2") (pin "2") (pinfunction "2_2") (pintype "passive"))
      (node (ref "C25") (pin "2") (pinfunction "2_2") (pintype "passive"))
      (node (ref "C3") (pin "2") (pinfunction "2_2") (pintype "passive"))
      (node (ref "C42") (pin "2") (pinfunction "2_2") (pintype "passive"))
      (node (ref "C43") (pin "2") (pinfunction "2_2") (pintype "passive"))
      (node (ref "C44") (pin "2") (pinfunction "2_2") (pintype "passive"))
      (node (ref "C46") (pin "1") (pinfunction "1_1") (pintype "passive"))
      (node (ref "C53") (pin "1") (pinfunction "1_1") (pintype "passive"))
      (node (ref "C54") (pin "1") (pinfunction "1_1") (pintype "passive"))
      (node (ref "C56") (pin "2") (pinfunction "2_2") (pintype "passive"))
      (node (ref "C57") (pin "2") (pinfunction "2_2") (pintype "passive"))
      (node (ref "C7") (pin "2") (pinfunction "2_2") (pintype "passive"))
      (node (ref "C9") (pin "2") (pinfunction "2_2") (pintype "passive"))
      (node (ref "D5") (pin "4") (pinfunction "C3_4") (pintype "passive"))
      (node (ref "L2") (pin "1") (pinfunction "1_1") (pintype "passive"))
      (node (ref "L3") (pin "P$1") (pinfunction "1_P$1") (pintype "passive"))
      (node (ref "P2") (pin "15") (pinfunction "15_15") (pintype "bidirectional"))
      (node (ref "P2") (pin "16") (pinfunction "16_16") (pintype "bidirectional"))
      (node (ref "PWR") (pin "+") (pinfunction "+_+") (pintype "passive"))
      (node (ref "Q3") (pin "2") (pinfunction "S_2") (pintype "passive"))
      (node (ref "R10") (pin "2") (pinfunction "2_2") (pintype "passive"))
      (node (ref "R11") (pin "2") (pinfunction "2_2") (pintype "passive"))
      (node (ref "R13") (pin "2") (pinfunction "2_2") (pintype "passive"))
      (node (ref "R14") (pin "2") (pinfunction "2_2") (pintype "passive"))
      (node (ref "R15") (pin "2") (pinfunction "2_2") (pintype "passive"))
      (node (ref "R19") (pin "2") (pinfunction "2_2") (pintype "passive"))
      (node (ref "R22") (pin "1") (pinfunction "1_1") (pintype "passive"))
      (node (ref "R24") (pin "2") (pinfunction "2_2") (pintype "passive"))
      (node (ref "R29") (pin "1") (pinfunction "1_1") (pintype "passive"))
      (node (ref "R30") (pin "1") (pinfunction "1_1") (pintype "passive"))
      (node (ref "R35") (pin "2") (pinfunction "2_2") (pintype "passive"))
      (node (ref "R44") (pin "2") (pinfunction "2_2") (pintype "passive"))
      (node (ref "R45") (pin "2") (pinfunction "2_2") (pintype "passive"))
      (node (ref "R47") (pin "2") (pinfunction "2_2") (pintype "passive"))
      (node (ref "R6") (pin "2") (pinfunction "2_2") (pintype "passive"))
      (node (ref "R7") (pin "1") (pinfunction "1_1") (pintype "passive"))
      (node (ref "TF") (pin "P4") (pinfunction "VDD_P4") (pintype "bidirectional"))
      (node (ref "U3") (pin "20") (pinfunction "VDD3P3_RTC_20") (pintype "bidirectional"))
      (node (ref "U3") (pin "46") (pinfunction "VDD3P3_CPU_46") (pintype "bidirectional"))
      (node (ref "U3") (pin "55") (pinfunction "VDDA_55") (pintype "bidirectional"))
      (node (ref "U3") (pin "56") (pinfunction "VDDA_56") (pintype "bidirectional"))
      (node (ref "U5") (pin "5") (pinfunction "VOUT_5") (pintype "bidirectional"))
      (node (ref "U7") (pin "12") (pinfunction "CS_12") (pintype "bidirectional"))
      (node (ref "U7") (pin "2") (pinfunction "SDX_2") (pintype "bidirectional"))
      (node (ref "U7") (pin "3") (pinfunction "SCX_3") (pintype "bidirectional"))
      (node (ref "U7") (pin "5") (pinfunction "VDDIO_5") (pintype "bidirectional"))
      (node (ref "U7") (pin "8") (pinfunction "VDD_8") (pintype "bidirectional"))
    )
    (net (code "2") (name "/CSI_1V2") (class "Default")
      (node (ref "C33") (pin "2") (pinfunction "2_2") (pintype "passive"))
      (node (ref "C34") (pin "2") (pinfunction "2_2") (pintype "passive"))
      (node (ref "J5") (pin "15") (pinfunction "15_15") (pintype "bidirectional"))
      (node (ref "U16") (pin "5") (pinfunction "VOUT_5") (pintype "bidirectional"))
    )
    (net (code "3") (name "/CSI_2V8") (class "Default")
      (node (ref "C32") (pin "2") (pinfunction "2_2") (pintype "passive"))
      (node (ref "J5") (pin "21") (pinfunction "21_21") (pintype "bidirectional"))
      (node (ref "U10") (pin "5") (pinfunction "VOUT_5") (pintype "bidirectional"))
    )
    (net (code "4") (name "/CSI_D0") (class "Default")
      (node (ref "J5") (pin "6") (pinfunction "6_6") (pintype "bidirectional"))
      (node (ref "U3") (pin "14") (pinfunction "GPIO9_14") (pintype "bidirectional"))
    )
    (net (code "5") (name "/CSI_D1") (class "Default")
      (node (ref "J5") (pin "4") (pinfunction "4_4") (pintype "bidirectional"))
      (node (ref "U3") (pin "16") (pinfunction "GPIO11_16") (pintype "bidirectional"))
    )
    (net (code "6") (name "/CSI_D2") (class "Default")
      (node (ref "J5") (pin "3") (pinfunction "3_3") (pintype "bidirectional"))
      (node (ref "U3") (pin "17") (pinfunction "GPIO12_17") (pintype "bidirectional"))
    )
    (net (code "7") (name "/CSI_D3") (class "Default")
      (node (ref "J5") (pin "5") (pinfunction "5_5") (pintype "bidirectional"))
      (node (ref "U3") (pin "15") (pinfunction "GPIO10_15") (pintype "bidirectional"))
    )
    (net (code "8") (name "/CSI_D4") (class "Default")
      (node (ref "J5") (pin "7") (pinfunction "7_7") (pintype "bidirectional"))
      (node (ref "U3") (pin "13") (pinfunction "GPIO8_13") (pintype "bidirectional"))
    )
    (net (code "9") (name "/CSI_D5") (class "Default")
      (node (ref "J5") (pin "9") (pinfunction "9_9") (pintype "bidirectional"))
      (node (ref "U3") (pin "11") (pinfunction "GPIO6_11") (pintype "bidirectional"))
    )
    (net (code "10") (name "/CSI_D6") (class "Default")
      (node (ref "J5") (pin "11") (pinfunction "11_11") (pintype "bidirectional"))
      (node (ref "U3") (pin "10") (pinfunction "GPIO5_10") (pintype "bidirectional"))
    )
    (net (code "11") (name "/CSI_D7") (class "Default")
      (node (ref "J5") (pin "13") (pinfunction "13_13") (pintype "bidirectional"))
      (node (ref "U3") (pin "8") (pinfunction "GPIO3_8") (pintype "bidirectional"))
    )
    (net (code "12") (name "/CSI_HSYNC") (class "Default")
      (node (ref "J5") (pin "16") (pinfunction "16_16") (pintype "bidirectional"))
      (node (ref "U3") (pin "7") (pinfunction "GPIO2_7") (pintype "bidirectional"))
    )
    (net (code "13") (name "/CSI_MCLK") (class "Default")
      (node (ref "J5") (pin "12") (pinfunction "12_12") (pintype "bidirectional"))
      (node (ref "U3") (pin "9") (pinfunction "GPIO4_9") (pintype "bidirectional"))
    )
    (net (code "14") (name "/CSI_PCLK") (class "Default")
      (node (ref "C35") (pin "2") (pinfunction "2_2") (pintype "passive"))
      (node (ref "J5") (pin "8") (pinfunction "8_8") (pintype "bidirectional"))
      (node (ref "U3") (pin "12") (pinfunction "GPIO7_12") (pintype "bidirectional"))
    )
    (net (code "15") (name "/CSI_RST") (class "Default")
      (node (ref "J5") (pin "19") (pinfunction "19_19") (pintype "bidirectional"))
      (node (ref "R22") (pin "2") (pinfunction "2_2") (pintype "passive"))
    )
    (net (code "16") (name "/CSI_VSYNC") (class "Default")
      (node (ref "J5") (pin "18") (pinfunction "18_18") (pintype "bidirectional"))
      (node (ref "U3") (pin "6") (pinfunction "GPIO1_6") (pintype "bidirectional"))
    )
    (net (code "17") (name "/GDR") (class "Default")
      (node (ref "P2") (pin "2") (pinfunction "2_2") (pintype "bidirectional"))
      (node (ref "Q12") (pin "1") (pinfunction "G_1") (pintype "passive"))
      (node (ref "R17") (pin "1") (pinfunction "1_1") (pintype "passive"))
    )
    (net (code "18") (name "/IO0") (class "Default")
      (node (ref "FLASH") (pin "2") (pinfunction "2_2") (pintype "passive"))
      (node (ref "Q3") (pin "1") (pinfunction "G_1") (pintype "passive"))
      (node (ref "R13") (pin "1") (pinfunction "1_1") (pintype "passive"))
      (node (ref "R6") (pin "1") (pinfunction "1_1") (pintype "passive"))
      (node (ref "U3") (pin "5") (pinfunction "GPIO0_5") (pintype "bidirectional"))
    )
    (net (code "19") (name "/IO13") (class "Default")
      (node (ref "D5") (pin "3") (pinfunction "C2_3") (pintype "passive"))
      (node (ref "R44") (pin "1") (pinfunction "1_1") (pintype "passive"))
      (node (ref "TF") (pin "P3") (pinfunction "CMD_P3") (pintype "bidirectional"))
      (node (ref "U3") (pin "18") (pinfunction "GPIO13_18") (pintype "bidirectional"))
    )
    (net (code "20") (name "/IO14") (class "Default")
      (node (ref "D5") (pin "5") (pinfunction "C4_5") (pintype "passive"))
      (node (ref "R45") (pin "1") (pinfunction "1_1") (pintype "passive"))
      (node (ref "TF") (pin "P5") (pinfunction "CLK_P5") (pintype "bidirectional"))
      (node (ref "U3") (pin "19") (pinfunction "GPIO14_19") (pintype "bidirectional"))
    )
    (net (code "21") (name "/IO15") (class "Default")
      (node (ref "D5") (pin "6") (pinfunction "C5_6") (pintype "passive"))
      (node (ref "R47") (pin "1") (pinfunction "1_1") (pintype "passive"))
      (node (ref "TF") (pin "P7") (pinfunction "DAT0_P7") (pintype "bidirectional"))
      (node (ref "U3") (pin "21") (pinfunction "XTAL_32K_P_21") (pintype "bidirectional"))
    )
    (net (code "22") (name "/IO16") (class "Default")
      (node (ref "C108") (pin "1") (pinfunction "1_1") (pintype "passive"))
      (node (ref "U3") (pin "22") (pinfunction "XTAL_32K_N_22") (pintype "bidirectional"))
      (node (ref "U6") (pin "5") (pinfunction "MCLK_5") (pintype "bidirectional"))
    )
    (net (code "23") (name "/IO19") (class "Default")
      (node (ref "R20") (pin "1") (pinfunction "1_1") (pintype "passive"))
      (node (ref "U3") (pin "25") (pinfunction "GPIO19_25") (pintype "bidirectional"))
    )
    (net (code "24") (name "/IO20") (class "Default")
      (node (ref "R21") (pin "1") (pinfunction "1_1") (pintype "passive"))
      (node (ref "U3") (pin "26") (pinfunction "GPIO20_26") (pintype "bidirectional"))
    )
    (net (code "25") (name "/IO21") (class "Default")
      (node (ref "R26") (pin "2") (pinfunction "2_2") (pintype "passive"))
      (node (ref "U3") (pin "27") (pinfunction "GPIO21_27") (pintype "bidirectional"))
    )
    (net (code "26") (name "/IO26{slash}SPICS1") (class "Default")
      (node (ref "U3") (pin "28") (pinfunction "SPICS1_28") (pintype "bidirectional"))
    )
    (net (code "27") (name "/IO38") (class "Default")
      (node (ref "P2") (pin "9") (pinfunction "9_9") (pintype "bidirectional"))
      (node (ref "U3") (pin "43") (pinfunction "GPIO38_43") (pintype "bidirectional"))
    )
    (net (code "28") (name "/IO39") (class "Default")
      (node (ref "P2") (pin "11") (pinfunction "11_11") (pintype "bidirectional"))
      (node (ref "U3") (pin "44") (pinfunction "MTCK_44") (pintype "bidirectional"))
    )
    (net (code "29") (name "/IO40") (class "Default")
      (node (ref "P2") (pin "12") (pinfunction "12_12") (pintype "bidirectional"))
      (node (ref "R30") (pin "2") (pinfunction "2_2") (pintype "passive"))
      (node (ref "U3") (pin "45") (pinfunction "MTDO_45") (pintype "bidirectional"))
    )
    (net (code "30") (name "/IO41") (class "Default")
      (node (ref "P2") (pin "13") (pinfunction "13_13") (pintype "bidirectional"))
      (node (ref "U3") (pin "47") (pinfunction "MTDI_47") (pintype "bidirectional"))
    )
    (net (code "31") (name "/IO42") (class "Default")
      (node (ref "P2") (pin "14") (pinfunction "14_14") (pintype "bidirectional"))
      (node (ref "U3") (pin "48") (pinfunction "MTMS_48") (pintype "bidirectional"))
    )
    (net (code "32") (name "/IO45") (class "Default")
      (node (ref "P2") (pin "10") (pinfunction "10_10") (pintype "bidirectional"))
      (node (ref "R11") (pin "1") (pinfunction "1_1") (pintype "passive"))
      (node (ref "R29") (pin "2") (pinfunction "2_2") (pintype "passive"))
      (node (ref "U3") (pin "51") (pinfunction "GPIO45_51") (pintype "bidirectional"))
    )
    (net (code "33") (name "/IO46") (class "Default")
      (node (ref "C80") (pin "1") (pinfunction "1_1") (pintype "passive"))
      (node (ref "U3") (pin "52") (pinfunction "GPIO46_52") (pintype "bidirectional"))
      (node (ref "U6") (pin "9") (pinfunction "SCLK_9") (pintype "bidirectional"))
    )
    (net (code "34") (name "/IO47") (class "Default")
      (node (ref "U3") (pin "37") (pinfunction "SPICLK_P_37") (pintype "bidirectional"))
      (node (ref "U6") (pin "10") (pinfunction "LRCK_10") (pintype "bidirectional"))
    )
    (net (code "35") (name "/IO48") (class "Default")
      (node (ref "R38") (pin "2") (pinfunction "2_2") (pintype "passive"))
      (node (ref "R40") (pin "2") (pinfunction "2_2") (pintype "passive"))
      (node (ref "U3") (pin "36") (pinfunction "SPICLK_N_36") (pintype "bidirectional"))
    )
    (net (code "36") (name "/MIC_1N") (class "Default")
      (node (ref "C67") (pin "1") (pinfunction "1_1") (pintype "passive"))
      (node (ref "C90") (pin "1") (pinfunction "1_1") (pintype "passive"))
    )
    (net (code "37") (name "/MIC_1P") (class "Default")
      (node (ref "C66") (pin "1") (pinfunction "1_1") (pintype "passive"))
      (node (ref "C89") (pin "1") (pinfunction "1_1") (pintype "passive"))
      (node (ref "C91") (pin "1") (pinfunction "1_1") (pintype "passive"))
    )
    (net (code "38") (name "/MIC_2N") (class "Default")
      (node (ref "C64") (pin "1") (pinfunction "1_1") (pintype "passive"))
      (node (ref "C83") (pin "1") (pinfunction "1_1") (pintype "passive"))
    )
    (net (code "39") (name "/MIC_2P") (class "Default")
      (node (ref "C65") (pin "1") (pinfunction "1_1") (pintype "passive"))
      (node (ref "C82") (pin "1") (pinfunction "1_1") (pintype "passive"))
      (node (ref "C84") (pin "1") (pinfunction "1_1") (pintype "passive"))
    )
    (net (code "40") (name "/MIC_3N") (class "Default")
      (node (ref "C71") (pin "1") (pinfunction "1_1") (pintype "passive"))
      (node (ref "C97") (pin "1") (pinfunction "1_1") (pintype "passive"))
    )
    (net (code "41") (name "/MIC_3P") (class "Default")
      (node (ref "C70") (pin "1") (pinfunction "1_1") (pintype "passive"))
      (node (ref "C72") (pin "1") (pinfunction "1_1") (pintype "passive"))
      (node (ref "C96") (pin "1") (pinfunction "1_1") (pintype "passive"))
    )
    (net (code "42") (name "/MIC_4N") (class "Default")
      (node (ref "C103") (pin "1") (pinfunction "1_1") (pintype "passive"))
      (node (ref "C69") (pin "1") (pinfunction "1_1") (pintype "passive"))
    )
    (net (code "43") (name "/MIC_4P") (class "Default")
      (node (ref "C101") (pin "1") (pinfunction "1_1") (pintype "passive"))
      (node (ref "C68") (pin "1") (pinfunction "1_1") (pintype "passive"))
      (node (ref "C81") (pin "1") (pinfunction "1_1") (pintype "passive"))
    )
    (net (code "44") (name "/MKF_3V3") (class "Default")
      (node (ref "C105") (pin "1") (pinfunction "1_1") (pintype "passive"))
      (node (ref "C107") (pin "1") (pinfunction "1_1") (pintype "passive"))
      (node (ref "C111") (pin "1") (pinfunction "1_1") (pintype "passive"))
      (node (ref "C20") (pin "1") (pinfunction "1_1") (pintype "passive"))
      (node (ref "C77") (pin "1") (pinfunction "1_1") (pintype "passive"))
      (node (ref "C79") (pin "1") (pinfunction "1_1") (pintype "passive"))
      (node (ref "R36") (pin "1") (pinfunction "1_1") (pintype "passive"))
      (node (ref "R5") (pin "1") (pinfunction "1_1") (pintype "passive"))
      (node (ref "U13") (pin "5") (pinfunction "VOUT_5") (pintype "bidirectional"))
      (node (ref "U6") (pin "22") (pinfunction "VDDA_22") (pintype "bidirectional"))
      (node (ref "U6") (pin "23") (pinfunction "VDDM_23") (pintype "bidirectional"))
      (node (ref "U6") (pin "6") (pinfunction "VDDP_6") (pintype "bidirectional"))
      (node (ref "U6") (pin "7") (pinfunction "VDDD_7") (pintype "bidirectional"))
    )
    (net (code "45") (name "/PREVGH") (class "Default")
      (node (ref "C52") (pin "1") (pinfunction "1_1") (pintype "passive"))
      (node (ref "D7") (pin "C") (pinfunction "C_C") (pintype "passive"))
      (node (ref "P2") (pin "21") (pinfunction "21_21") (pintype "bidirectional"))
    )
    (net (code "46") (name "/PREVGL") (class "Default")
      (node (ref "C55") (pin "1") (pinfunction "1_1") (pintype "passive"))
      (node (ref "D6") (pin "A") (pinfunction "A_A") (pintype "passive"))
      (node (ref "P2") (pin "23") (pinfunction "23_23") (pintype "bidirectional"))
    )
    (net (code "47") (name "/PWDN") (class "Default")
      (node (ref "J5") (pin "17") (pinfunction "17_17") (pintype "bidirectional"))
      (node (ref "R27") (pin "1") (pinfunction "1_1") (pintype "passive"))
    )
    (net (code "48") (name "/RESE") (class "Default")
      (node (ref "P2") (pin "3") (pinfunction "3_3") (pintype "bidirectional"))
      (node (ref "Q12") (pin "2") (pinfunction "S_2") (pintype "passive"))
      (node (ref "R33") (pin "1") (pinfunction "1_1") (pintype "passive"))
    )
    (net (code "49") (name "/RESET") (class "Default")
      (node (ref "C10") (pin "2") (pinfunction "2_2") (pintype "passive"))
      (node (ref "R15") (pin "1") (pinfunction "1_1") (pintype "passive"))
      (node (ref "RST") (pin "2") (pinfunction "2_2") (pintype "passive"))
      (node (ref "U3") (pin "4") (pinfunction "CHIP_PU_4") (pintype "bidirectional"))
    )
    (net (code "50") (name "/SPICLK") (class "Default")
      (node (ref "R18") (pin "1") (pinfunction "1_1") (pintype "passive"))
      (node (ref "U4") (pin "6") (pinfunction "CLK_6") (pintype "bidirectional"))
    )
    (net (code "51") (name "/SPICS0") (class "Default")
      (node (ref "U3") (pin "32") (pinfunction "SPICS0_32") (pintype "bidirectional"))
      (node (ref "U4") (pin "1") (pinfunction "/CS_1") (pintype "bidirectional"))
    )
    (net (code "52") (name "/SPID") (class "Default")
      (node (ref "R28") (pin "1") (pinfunction "1_1") (pintype "passive"))
      (node (ref "U4") (pin "5") (pinfunction "DI(IO0)_5") (pintype "bidirectional"))
    )
    (net (code "53") (name "/SPIHD") (class "Default")
      (node (ref "R25") (pin "1") (pinfunction "1_1") (pintype "passive"))
      (node (ref "U4") (pin "7") (pinfunction "/HOLD/RESET(IO3)_7") (pintype "bidirectional"))
    )
    (net (code "54") (name "/SPIQ") (class "Default")
      (node (ref "R16") (pin "1") (pinfunction "1_1") (pintype "passive"))
      (node (ref "U4") (pin "2") (pinfunction "DO(IO1)_2") (pintype "bidirectional"))
    )
    (net (code "55") (name "/SPIWP") (class "Default")
      (node (ref "R23") (pin "1") (pinfunction "1_1") (pintype "passive"))
      (node (ref "U4") (pin "3") (pinfunction "/WP(IO2)_3") (pintype "bidirectional"))
    )
    (net (code "56") (name "/U0RXD") (class "Default")
      (node (ref "R39") (pin "2") (pinfunction "2_2") (pintype "passive"))
      (node (ref "RX") (pin "T") (pinfunction "T_T") (pintype "bidirectional"))
      (node (ref "U3") (pin "50") (pinfunction "U0RXD_50") (pintype "bidirectional"))
    )
    (net (code "57") (name "/U0TXD") (class "Default")
      (node (ref "R12") (pin "1") (pinfunction "1_1") (pintype "passive"))
      (node (ref "TX") (pin "T") (pinfunction "T_T") (pintype "bidirectional"))
    )
    (net (code "58") (name "/USB_D+") (class "Default")
      (node (ref "R21") (pin "2") (pinfunction "2_2") (pintype "passive"))
      (node (ref "USB1") (pin "A6") (pinfunction "D+_A6") (pintype "bidirectional"))
      (node (ref "USB1") (pin "B6") (pinfunction "D+_B6") (pintype "bidirectional"))
    )
    (net (code "59") (name "/USB_D-") (class "Default")
      (node (ref "R20") (pin "2") (pinfunction "2_2") (pintype "passive"))
      (node (ref "USB1") (pin "A7") (pinfunction "D-_A7") (pintype "bidirectional"))
      (node (ref "USB1") (pin "B7") (pinfunction "D-_B7") (pintype "bidirectional"))
    )
    (net (code "60") (name "/VCOM") (class "Default")
      (node (ref "C51") (pin "1") (pinfunction "1_1") (pintype "passive"))
      (node (ref "P2") (pin "24") (pinfunction "24_24") (pintype "bidirectional"))
    )
    (net (code "61") (name "/VDD_CAM") (class "Default")
      (node (ref "C27") (pin "2") (pinfunction "2_2") (pintype "passive"))
      (node (ref "C28") (pin "2") (pinfunction "2_2") (pintype "passive"))
      (node (ref "C29") (pin "2") (pinfunction "2_2") (pintype "passive"))
      (node (ref "C30") (pin "2") (pinfunction "2_2") (pintype "passive"))
      (node (ref "J5") (pin "14") (pinfunction "14_14") (pintype "bidirectional"))
      (node (ref "Q3") (pin "3") (pinfunction "D_3") (pintype "passive"))
      (node (ref "U10") (pin "1") (pinfunction "VIN_1") (pintype "bidirectional"))
      (node (ref "U10") (pin "3") (pinfunction "EN_3") (pintype "bidirectional"))
      (node (ref "U16") (pin "1") (pinfunction "VIN_1") (pintype "bidirectional"))
      (node (ref "U16") (pin "3") (pinfunction "EN_3") (pintype "bidirectional"))
    )
    (net (code "62") (name "/VDD_SPI") (class "Default")
      (node (ref "C12") (pin "2") (pinfunction "2_2") (pintype "passive"))
      (node (ref "C22") (pin "1") (pinfunction "1_1") (pintype "passive"))
      (node (ref "U3") (pin "29") (pinfunction "VDD_SPI_29") (pintype "bidirectional"))
      (node (ref "U4") (pin "8") (pinfunction "VCC_8") (pintype "bidirectional"))
    )
    (net (code "63") (name "/VMIC12") (class "Default")
      (node (ref "C63") (pin "2") (pinfunction "2_2") (pintype "passive"))
      (node (ref "C73") (pin "1") (pinfunction "1_1") (pintype "passive"))
      (node (ref "C74") (pin "1") (pinfunction "1_1") (pintype "passive"))
      (node (ref "C85") (pin "1") (pinfunction "1_1") (pintype "passive"))
      (node (ref "C86") (pin "1") (pinfunction "1_1") (pintype "passive"))
      (node (ref "MIC1") (pin "1") (pinfunction "VDD_1") (pintype "bidirectional"))
      (node (ref "MIC2") (pin "1") (pinfunction "VDD_1") (pintype "bidirectional"))
      (node (ref "U6") (pin "24") (pinfunction "MICBIAS12_24") (pintype "bidirectional"))
    )
    (net (code "64") (name "/VMIC34") (class "Default")
      (node (ref "C62") (pin "2") (pinfunction "2_2") (pintype "passive"))
      (node (ref "C78") (pin "1") (pinfunction "1_1") (pintype "passive"))
      (node (ref "C92") (pin "1") (pinfunction "1_1") (pintype "passive"))
      (node (ref "C93") (pin "1") (pinfunction "1_1") (pintype "passive"))
      (node (ref "C99") (pin "1") (pinfunction "1_1") (pintype "passive"))
      (node (ref "MIC3") (pin "1") (pinfunction "VDD_1") (pintype "bidirectional"))
      (node (ref "MIC4") (pin "1") (pinfunction "VDD_1") (pintype "bidirectional"))
      (node (ref "U6") (pin "26") (pinfunction "MICBIAS34_26") (pintype "bidirectional"))
    )
    (net (code "65") (name "/VPWR") (class "Default")
      (node (ref "C106") (pin "1") (pinfunction "1_1") (pintype "passive"))
      (node (ref "C16") (pin "2") (pinfunction "2_2") (pintype "passive"))
      (node (ref "C24") (pin "2") (pinfunction "2_2") (pintype "passive"))
      (node (ref "C38") (pin "2") (pinfunction "2_2") (pintype "passive"))
      (node (ref "C39") (pin "1") (pinfunction "1_1") (pintype "passive"))
      (node (ref "D2") (pin "-") (pinfunction "-_-") (pintype "passive"))
      (node (ref "Q1") (pin "2") (pinfunction "S_2") (pintype "passive"))
      (node (ref "U13") (pin "1") (pinfunction "VIN_1") (pintype "bidirectional"))
      (node (ref "U13") (pin "3") (pinfunction "EN_3") (pintype "bidirectional"))
      (node (ref "U5") (pin "1") (pinfunction "VIN_1") (pintype "bidirectional"))
      (node (ref "U5") (pin "3") (pinfunction "EN_3") (pintype "bidirectional"))
    )
    (net (code "66") (name "3.3V") (class "Default")
      (node (ref "R7") (pin "2") (pinfunction "2_2") (pintype "passive"))
    )
    (net (code "67") (name "5V") (class "Default")
      (node (ref "C104") (pin "1") (pinfunction "1_1") (pintype "passive"))
      (node (ref "C14") (pin "1") (pinfunction "1_1") (pintype "passive"))
      (node (ref "C21") (pin "1") (pinfunction "1_1") (pintype "passive"))
      (node (ref "C23") (pin "1") (pinfunction "1_1") (pintype "passive"))
      (node (ref "C26") (pin "2") (pinfunction "2_2") (pintype "passive"))
      (node (ref "C31") (pin "2") (pinfunction "2_2") (pintype "passive"))
      (node (ref "CHRG") (pin "A") (pinfunction "A_A") (pintype "passive"))
      (node (ref "D2") (pin "+") (pinfunction "+_+") (pintype "passive"))
      (node (ref "DONE") (pin "A") (pinfunction "A_A") (pintype "passive"))
      (node (ref "Q1") (pin "1") (pinfunction "G_1") (pintype "passive"))
      (node (ref "R9") (pin "2") (pinfunction "2_2") (pintype "passive"))
      (node (ref "U2") (pin "4") (pinfunction "VIN_4") (pintype "bidirectional"))
      (node (ref "U2") (pin "8") (pinfunction "CE_8") (pintype "bidirectional"))
      (node (ref "USB1") (pin "VBUS1") (pinfunction "VBUS_VBUS1") (pintype "bidirectional"))
      (node (ref "USB1") (pin "VBUS2") (pinfunction "VBUS_VBUS2") (pintype "bidirectional"))
    )
    (net (code "68") (name "AGND") (class "Default")
      (node (ref "C100") (pin "2") (pinfunction "2_2") (pintype "passive"))
      (node (ref "C101") (pin "2") (pinfunction "2_2") (pintype "passive"))
      (node (ref "C102") (pin "2") (pinfunction "2_2") (pintype "passive"))
      (node (ref "C103") (pin "2") (pinfunction "2_2") (pintype "passive"))
      (node (ref "C108") (pin "2") (pinfunction "2_2") (pintype "passive"))
      (node (ref "C111") (pin "2") (pinfunction "2_2") (pintype "passive"))
      (node (ref "C20") (pin "2") (pinfunction "2_2") (pintype "passive"))
      (node (ref "C40") (pin "2") (pinfunction "2_2") (pintype "passive"))
      (node (ref "C41") (pin "2") (pinfunction "2_2") (pintype "passive"))
      (node (ref "C59") (pin "2") (pinfunction "2_2") (pintype "passive"))
      (node (ref "C60") (pin "2") (pinfunction "2_2") (pintype "passive"))
      (node (ref "C62") (pin "1") (pinfunction "1_1") (pintype "passive"))
      (node (ref "C63") (pin "1") (pinfunction "1_1") (pintype "passive"))
      (node (ref "C73") (pin "2") (pinfunction "2_2") (pintype "passive"))
      (node (ref "C74") (pin "2") (pinfunction "2_2") (pintype "passive"))
      (node (ref "C75") (pin "2") (pinfunction "2_2") (pintype "passive"))
      (node (ref "C76") (pin "2") (pinfunction "2_2") (pintype "passive"))
      (node (ref "C77") (pin "2") (pinfunction "2_2") (pintype "passive"))
      (node (ref "C78") (pin "2") (pinfunction "2_2") (pintype "passive"))
      (node (ref "C79") (pin "2") (pinfunction "2_2") (pintype "passive"))
      (node (ref "C80") (pin "2") (pinfunction "2_2") (pintype "passive"))
      (node (ref "C82") (pin "2") (pinfunction "2_2") (pintype "passive"))
      (node (ref "C83") (pin "2") (pinfunction "2_2") (pintype "passive"))
      (node (ref "C85") (pin "2") (pinfunction "2_2") (pintype "passive"))
      (node (ref "C86") (pin "2") (pinfunction "2_2") (pintype "passive"))
      (node (ref "C87") (pin "2") (pinfunction "2_2") (pintype "passive"))
      (node (ref "C88") (pin "2") (pinfunction "2_2") (pintype "passive"))
      (node (ref "C89") (pin "2") (pinfunction "2_2") (pintype "passive"))
      (node (ref "C90") (pin "2") (pinfunction "2_2") (pintype "passive"))
      (node (ref "C92") (pin "2") (pinfunction "2_2") (pintype "passive"))
      (node (ref "C93") (pin "2") (pinfunction "2_2") (pintype "passive"))
      (node (ref "C94") (pin "2") (pinfunction "2_2") (pintype "passive"))
      (node (ref "C95") (pin "2") (pinfunction "2_2") (pintype "passive"))
      (node (ref "C96") (pin "2") (pinfunction "2_2") (pintype "passive"))
      (node (ref "C97") (pin "2") (pinfunction "2_2") (pintype "passive"))
      (node (ref "C98") (pin "2") (pinfunction "2_2") (pintype "passive"))
      (node (ref "C99") (pin "2") (pinfunction "2_2") (pintype "passive"))
      (node (ref "MIC1") (pin "2") (pinfunction "GND_2") (pintype "bidirectional"))
      (node (ref "MIC1") (pin "3") (pinfunction "GND_3") (pintype "bidirectional"))
      (node (ref "MIC2") (pin "2") (pinfunction "GND_2") (pintype "bidirectional"))
      (node (ref "MIC2") (pin "3") (pinfunction "GND_3") (pintype "bidirectional"))
      (node (ref "MIC3") (pin "2") (pinfunction "GND_2") (pintype "bidirectional"))
      (node (ref "MIC3") (pin "3") (pinfunction "GND_3") (pintype "bidirectional"))
      (node (ref "MIC4") (pin "2") (pinfunction "GND_2") (pintype "bidirectional"))
      (node (ref "MIC4") (pin "3") (pinfunction "GND_3") (pintype "bidirectional"))
      (node (ref "R3") (pin "1") (pinfunction "1_1") (pintype "passive"))
      (node (ref "R42") (pin "1") (pinfunction "1_1") (pintype "passive"))
      (node (ref "R8") (pin "1") (pinfunction "1_1") (pintype "passive"))
      (node (ref "U6") (pin "21") (pinfunction "GNDA_21") (pintype "bidirectional"))
      (node (ref "U6") (pin "33") (pinfunction "EP_33") (pintype "bidirectional"))
      (node (ref "U6") (pin "8") (pinfunction "GNDD_8") (pintype "bidirectional"))
    )
    (net (code "69") (name "GND") (class "Default")
      (node (ref "ANT1") (pin "GND") (pinfunction "GND_GND") (pintype "passive"))
      (node (ref "BAT") (pin "-") (pinfunction "2_-") (pintype "bidirectional"))
      (node (ref "BAT") (pin "3") (pinfunction "3_3") (pintype "bidirectional"))
      (node (ref "BAT") (pin "4") (pinfunction "4_4") (pintype "bidirectional"))
      (node (ref "C1") (pin "1") (pinfunction "1_1") (pintype "passive"))
      (node (ref "C10") (pin "1") (pinfunction "1_1") (pintype "passive"))
      (node (ref "C104") (pin "2") (pinfunction "2_2") (pintype "passive"))
      (node (ref "C105") (pin "2") (pinfunction "2_2") (pintype "passive"))
      (node (ref "C106") (pin "2") (pinfunction "2_2") (pintype "passive"))
      (node (ref "C107") (pin "2") (pinfunction "2_2") (pintype "passive"))
      (node (ref "C11") (pin "1") (pinfunction "1_1") (pintype "passive"))
      (node (ref "C12") (pin "1") (pinfunction "1_1") (pintype "passive"))
      (node (ref "C13") (pin "1") (pinfunction "1_1") (pintype "passive"))
      (node (ref "C14") (pin "2") (pinfunction "2_2") (pintype "passive"))
      (node (ref "C15") (pin "1") (pinfunction "1_1") (pintype "passive"))
      (node (ref "C16") (pin "1") (pinfunction "1_1") (pintype "passive"))
      (node (ref "C17") (pin "1") (pinfunction "1_1") (pintype "passive"))
      (node (ref "C18") (pin "1") (pinfunction "1_1") (pintype "passive"))
      (node (ref "C19") (pin "2") (pinfunction "2_2") (pintype "passive"))
      (node (ref "C2") (pin "1") (pinfunction "1_1") (pintype "passive"))
      (node (ref "C21") (pin "2") (pinfunction "2_2") (pintype "passive"))
      (node (ref "C22") (pin "2") (pinfunction "2_2") (pintype "passive"))
      (node (ref "C23") (pin "2") (pinfunction "2_2") (pintype "passive"))
      (node (ref "C24") (pin "1") (pinfunction "1_1") (pintype "passive"))
      (node (ref "C25") (pin "1") (pinfunction "1_1") (pintype "passive"))
      (node (ref "C26") (pin "1") (pinfunction "1_1") (pintype "passive"))
      (node (ref "C27") (pin "1") (pinfunction "1_1") (pintype "passive"))
      (node (ref "C28") (pin "1") (pinfunction "1_1") (pintype "passive"))
      (node (ref "C29") (pin "1") (pinfunction "1_1") (pintype "passive"))
      (node (ref "C3") (pin "1") (pinfunction "1_1") (pintype "passive"))
      (node (ref "C30") (pin "1") (pinfunction "1_1") (pintype "passive"))
      (node (ref "C31") (pin "1") (pinfunction "1_1") (pintype "passive"))
      (node (ref "C32") (pin "1") (pinfunction "1_1") (pintype "passive"))
      (node (ref "C33") (pin "1") (pinfunction "1_1") (pintype "passive"))
      (node (ref "C34") (pin "1") (pinfunction "1_1") (pintype "passive"))
      (node (ref "C35") (pin "1") (pinfunction "1_1") (pintype "passive"))
      (node (ref "C36") (pin "2") (pinfunction "2_2") (pintype "passive"))
      (node (ref "C38") (pin "1") (pinfunction "1_1") (pintype "passive"))
      (node (ref "C39") (pin "2") (pinfunction "2_2") (pintype "passive"))
      (node (ref "C4") (pin "1") (pinfunction "1_1") (pintype "passive"))
      (node (ref "C42") (pin "1") (pinfunction "1_1") (pintype "passive"))
      (node (ref "C43") (pin "1") (pinfunction "1_1") (pintype "passive"))
      (node (ref "C44") (pin "1") (pinfunction "1_1") (pintype "passive"))
      (node (ref "C45") (pin "2") (pinfunction "2_2") (pintype "passive"))
      (node (ref "C46") (pin "2") (pinfunction "2_2") (pintype "passive"))
      (node (ref "C47") (pin "2") (pinfunction "2_2") (pintype "passive"))
      (node (ref "C48") (pin "2") (pinfunction "2_2") (pintype "passive"))
      (node (ref "C49") (pin "2") (pinfunction "2_2") (pintype "passive"))
      (node (ref "C5") (pin "1") (pinfunction "1_1") (pintype "passive"))
      (node (ref "C50") (pin "2") (pinfunction "2_2") (pintype "passive"))
      (node (ref "C51") (pin "2") (pinfunction "2_2") (pintype "passive"))
      (node (ref "C52") (pin "2") (pinfunction "2_2") (pintype "passive"))
      (node (ref "C53") (pin "2") (pinfunction "2_2") (pintype "passive"))
      (node (ref "C54") (pin "2") (pinfunction "2_2") (pintype "passive"))
      (node (ref "C55") (pin "2") (pinfunction "2_2") (pintype "passive"))
      (node (ref "C56") (pin "1") (pinfunction "1_1") (pintype "passive"))
      (node (ref "C57") (pin "1") (pinfunction "1_1") (pintype "passive"))
      (node (ref "C6") (pin "2") (pinfunction "2_2") (pintype "passive"))
      (node (ref "C7") (pin "1") (pinfunction "1_1") (pintype "passive"))
      (node (ref "C8") (pin "1") (pinfunction "1_1") (pintype "passive"))
      (node (ref "C9") (pin "1") (pinfunction "1_1") (pintype "passive"))
      (node (ref "D4") (pin "C") (pinfunction "C_C") (pintype "passive"))
      (node (ref "D5") (pin "2") (pinfunction "A_2") (pintype "passive"))
      (node (ref "FLASH") (pin "1") (pinfunction "1_1") (pintype "passive"))
      (node (ref "J5") (pin "10") (pinfunction "10_10") (pintype "bidirectional"))
      (node (ref "J5") (pin "23") (pinfunction "23_23") (pintype "bidirectional"))
      (node (ref "J5") (pin "25") (pinfunction "25_25") (pintype "bidirectional"))
      (node (ref "J5") (pin "26") (pinfunction "26_26") (pintype "bidirectional"))
      (node (ref "P2") (pin "17") (pinfunction "17_17") (pintype "bidirectional"))
      (node (ref "P2") (pin "25") (pinfunction "25_25") (pintype "bidirectional"))
      (node (ref "P2") (pin "26") (pinfunction "26_26") (pintype "bidirectional"))
      (node (ref "P2") (pin "8") (pinfunction "8_8") (pintype "bidirectional"))
      (node (ref "R1") (pin "1") (pinfunction "1_1") (pintype "passive"))
      (node (ref "R17") (pin "2") (pinfunction "2_2") (pintype "passive"))
      (node (ref "R2") (pin "1") (pinfunction "1_1") (pintype "passive"))
      (node (ref "R27") (pin "2") (pinfunction "2_2") (pintype "passive"))
      (node (ref "R31") (pin "2") (pinfunction "2_2") (pintype "passive"))
      (node (ref "R32") (pin "2") (pinfunction "2_2") (pintype "passive"))
      (node (ref "R33") (pin "2") (pinfunction "2_2") (pintype "passive"))
      (node (ref "R8") (pin "2") (pinfunction "2_2") (pintype "passive"))
      (node (ref "R9") (pin "1") (pinfunction "1_1") (pintype "passive"))
      (node (ref "RST") (pin "1") (pinfunction "1_1") (pintype "passive"))
      (node (ref "S1") (pin "1") (pinfunction "1_1") (pintype "bidirectional"))
      (node (ref "S2") (pin "1") (pinfunction "1_1") (pintype "bidirectional"))
      (node (ref "S3") (pin "1") (pinfunction "1_1") (pintype "bidirectional"))
      (node (ref "S4") (pin "1") (pinfunction "1_1") (pintype "bidirectional"))
      (node (ref "TF") (pin "1") (pinfunction "GND_1") (pintype "bidirectional"))
      (node (ref "TF") (pin "2") (pinfunction "GND_2") (pintype "bidirectional"))
      (node (ref "TF") (pin "3") (pinfunction "GND_3") (pintype "bidirectional"))
      (node (ref "TF") (pin "4") (pinfunction "GND_4") (pintype "bidirectional"))
      (node (ref "TF") (pin "P6") (pinfunction "VSS_P6") (pintype "bidirectional"))
      (node (ref "U1") (pin "1") (pinfunction "CTG_1") (pintype "input"))
      (node (ref "U1") (pin "4") (pinfunction "GND_4") (pintype "bidirectional"))
      (node (ref "U1") (pin "6") (pinfunction "QSTRT_6") (pintype "bidirectional"))
      (node (ref "U1") (pin "9") (pinfunction "GND_9") (pintype "bidirectional"))
      (node (ref "U10") (pin "2") (pinfunction "GND_2") (pintype "bidirectional"))
      (node (ref "U13") (pin "2") (pinfunction "GND_2") (pintype "bidirectional"))
      (node (ref "U16") (pin "2") (pinfunction "GND_2") (pintype "bidirectional"))
      (node (ref "U2") (pin "1") (pinfunction "TEMP_1") (pintype "bidirectional"))
      (node (ref "U2") (pin "3") (pinfunction "GND_3") (pintype "bidirectional"))
      (node (ref "U2") (pin "9") (pinfunction "GND_9") (pintype "bidirectional"))
      (node (ref "U3") (pin "57") (pinfunction "GND_57") (pintype "bidirectional"))
      (node (ref "U4") (pin "4") (pinfunction "GND_4") (pintype "bidirectional"))
      (node (ref "U5") (pin "2") (pinfunction "GND_2") (pintype "bidirectional"))
      (node (ref "U7") (pin "1") (pinfunction "SDO/SA0_1") (pintype "bidirectional"))
      (node (ref "U7") (pin "6") (pinfunction "GND1_6") (pintype "bidirectional"))
      (node (ref "U7") (pin "7") (pinfunction "GND2_7") (pintype "bidirectional"))
      (node (ref "USB1") (pin "GND") (pinfunction "GND_GND") (pintype "bidirectional"))
      (node (ref "USB1") (pin "GND2") (pinfunction "GND_GND2") (pintype "bidirectional"))
      (node (ref "USB1") (pin "P$1") (pinfunction "SHLD_P$1") (pintype "bidirectional"))
      (node (ref "USB1") (pin "P$2") (pinfunction "SHLD_P$2") (pintype "bidirectional"))
      (node (ref "USB1") (pin "P$3") (pinfunction "SHLD_P$3") (pintype "bidirectional"))
      (node (ref "USB1") (pin "P$4") (pinfunction "SHLD_P$4") (pintype "bidirectional"))
      (node (ref "X1") (pin "2") (pinfunction "G2_2") (pintype "power_in"))
      (node (ref "X1") (pin "4") (pinfunction "G1_4") (pintype "power_in"))
    )
    (net (code "70") (name "IO17{slash}I2C_SDA") (class "Default")
      (node (ref "J5") (pin "22") (pinfunction "22_22") (pintype "bidirectional"))
      (node (ref "R24") (pin "1") (pinfunction "1_1") (pintype "passive"))
      (node (ref "U1") (pin "8") (pinfunction "SDA_8") (pintype "input"))
      (node (ref "U3") (pin "23") (pinfunction "GPIO17_23") (pintype "bidirectional"))
      (node (ref "U6") (pin "3") (pinfunction "CDATA_3") (pintype "bidirectional"))
      (node (ref "U7") (pin "14") (pinfunction "SDA_14") (pintype "bidirectional"))
    )
    (net (code "71") (name "IO18{slash}I2C_SCL") (class "Default")
      (node (ref "J5") (pin "20") (pinfunction "20_20") (pintype "bidirectional"))
      (node (ref "R19") (pin "1") (pinfunction "1_1") (pintype "passive"))
      (node (ref "U1") (pin "7") (pinfunction "SCL_7") (pintype "output"))
      (node (ref "U3") (pin "24") (pinfunction "GPIO18_24") (pintype "bidirectional"))
      (node (ref "U6") (pin "4") (pinfunction "CCLK_4") (pintype "bidirectional"))
      (node (ref "U7") (pin "13") (pinfunction "SCL_13") (pintype "bidirectional"))
    )
    (net (code "72") (name "Net-(ANT1-PadFEED)") (class "Default")
      (node (ref "ANT1") (pin "FEED") (pinfunction "FEED_FEED") (pintype "passive"))
      (node (ref "C18") (pin "2") (pinfunction "2_2") (pintype "passive"))
      (node (ref "L1") (pin "1") (pinfunction "1_1") (pintype "passive"))
      (node (ref "L4") (pin "2") (pinfunction "2_2") (pintype "passive"))
    )
    (net (code "73") (name "Net-(C4-Pad2)") (class "Default")
      (node (ref "C4") (pin "2") (pinfunction "2_2") (pintype "passive"))
      (node (ref "L2") (pin "2") (pinfunction "2_2") (pintype "passive"))
      (node (ref "U3") (pin "2") (pinfunction "VDD3P3_2") (pintype "bidirectional"))
      (node (ref "U3") (pin "3") (pinfunction "VDD3P3_3") (pintype "bidirectional"))
    )
    (net (code "74") (name "Net-(C8-Pad2)") (class "Default")
      (node (ref "C8") (pin "2") (pinfunction "2_2") (pintype "passive"))
      (node (ref "L4") (pin "1") (pinfunction "1_1") (pintype "passive"))
    )
    (net (code "75") (name "Net-(C45-Pad1)") (class "Default")
      (node (ref "C45") (pin "1") (pinfunction "1_1") (pintype "passive"))
      (node (ref "P2") (pin "5") (pinfunction "5_5") (pintype "bidirectional"))
    )
    (net (code "76") (name "Net-(C47-Pad1)") (class "Default")
      (node (ref "C47") (pin "1") (pinfunction "1_1") (pintype "passive"))
      (node (ref "P2") (pin "18") (pinfunction "18_18") (pintype "bidirectional"))
    )
    (net (code "77") (name "Net-(C48-Pad1)") (class "Default")
      (node (ref "C48") (pin "1") (pinfunction "1_1") (pintype "passive"))
      (node (ref "P2") (pin "19") (pinfunction "19_19") (pintype "bidirectional"))
    )
    (net (code "78") (name "Net-(C49-Pad1)") (class "Default")
      (node (ref "C49") (pin "1") (pinfunction "1_1") (pintype "passive"))
      (node (ref "P2") (pin "20") (pinfunction "20_20") (pintype "bidirectional"))
    )
    (net (code "79") (name "Net-(C50-Pad1)") (class "Default")
      (node (ref "C50") (pin "1") (pinfunction "1_1") (pintype "passive"))
      (node (ref "P2") (pin "22") (pinfunction "22_22") (pintype "bidirectional"))
    )
    (net (code "80") (name "Net-(C58-Pad1)") (class "Default")
      (node (ref "C58") (pin "1") (pinfunction "1_1") (pintype "passive"))
      (node (ref "D4") (pin "A") (pinfunction "A_A") (pintype "passive"))
      (node (ref "D6") (pin "C") (pinfunction "C_C") (pintype "passive"))
    )
    (net (code "81") (name "Net-(C72-Pad2)") (class "Default")
      (node (ref "C72") (pin "2") (pinfunction "2_2") (pintype "passive"))
      (node (ref "C95") (pin "1") (pinfunction "1_1") (pintype "passive"))
      (node (ref "L7") (pin "2") (pinfunction "2_2") (pintype "passive"))
    )
    (net (code "82") (name "Net-(C76-Pad1)") (class "Default")
      (node (ref "C76") (pin "1") (pinfunction "1_1") (pintype "passive"))
      (node (ref "C84") (pin "2") (pinfunction "2_2") (pintype "passive"))
      (node (ref "L5") (pin "2") (pinfunction "2_2") (pintype "passive"))
    )
    (net (code "83") (name "Net-(C88-Pad1)") (class "Default")
      (node (ref "C88") (pin "1") (pinfunction "1_1") (pintype "passive"))
      (node (ref "C91") (pin "2") (pinfunction "2_2") (pintype "passive"))
      (node (ref "L6") (pin "2") (pinfunction "2_2") (pintype "passive"))
    )
    (net (code "84") (name "Net-(C100-Pad1)") (class "Default")
      (node (ref "C100") (pin "1") (pinfunction "1_1") (pintype "passive"))
      (node (ref "C81") (pin "2") (pinfunction "2_2") (pintype "passive"))
      (node (ref "L8") (pin "2") (pinfunction "2_2") (pintype "passive"))
    )
    (net (code "85") (name "Net-(CHRG-PadC)") (class "Default")
      (node (ref "CHRG") (pin "C") (pinfunction "C_C") (pintype "passive"))
      (node (ref "R41") (pin "2") (pinfunction "2_2") (pintype "passive"))
    )
    (net (code "86") (name "Net-(D5-C1)") (class "Default")
      (node (ref "D5") (pin "1") (pinfunction "C1_1") (pintype "passive"))
      (node (ref "R35") (pin "1") (pinfunction "1_1") (pintype "passive"))
    )
    (net (code "87") (name "Net-(DONE-PadC)") (class "Default")
      (node (ref "DONE") (pin "C") (pinfunction "C_C") (pintype "passive"))
      (node (ref "R4") (pin "2") (pinfunction "2_2") (pintype "passive"))
    )
    (net (code "88") (name "Net-(L3-2)") (class "Default")
      (node (ref "C58") (pin "2") (pinfunction "2_2") (pintype "passive"))
      (node (ref "D7") (pin "A") (pinfunction "A_A") (pintype "passive"))
      (node (ref "L3") (pin "P$2") (pinfunction "2_P$2") (pintype "passive"))
      (node (ref "Q12") (pin "3") (pinfunction "D_3") (pintype "passive"))
    )
    (net (code "89") (name "Net-(MIC1-OUT)") (class "Default")
      (node (ref "C75") (pin "1") (pinfunction "1_1") (pintype "passive"))
      (node (ref "L5") (pin "1") (pinfunction "1_1") (pintype "passive"))
      (node (ref "MIC1") (pin "4") (pinfunction "OUT_4") (pintype "bidirectional"))
    )
    (net (code "90") (name "Net-(MIC2-OUT)") (class "Default")
      (node (ref "C87") (pin "1") (pinfunction "1_1") (pintype "passive"))
      (node (ref "L6") (pin "1") (pinfunction "1_1") (pintype "passive"))
      (node (ref "MIC2") (pin "4") (pinfunction "OUT_4") (pintype "bidirectional"))
    )
    (net (code "91") (name "Net-(MIC3-OUT)") (class "Default")
      (node (ref "C94") (pin "1") (pinfunction "1_1") (pintype "passive"))
      (node (ref "L7") (pin "1") (pinfunction "1_1") (pintype "passive"))
      (node (ref "MIC3") (pin "4") (pinfunction "OUT_4") (pintype "bidirectional"))
    )
    (net (code "92") (name "Net-(MIC4-OUT)") (class "Default")
      (node (ref "C102") (pin "1") (pinfunction "1_1") (pintype "passive"))
      (node (ref "L8") (pin "1") (pinfunction "1_1") (pintype "passive"))
      (node (ref "MIC4") (pin "4") (pinfunction "OUT_4") (pintype "bidirectional"))
    )
    (net (code "93") (name "Net-(PWR-Pad-)") (class "Default")
      (node (ref "PWR") (pin "-") (pinfunction "-_-") (pintype "passive"))
      (node (ref "R1") (pin "2") (pinfunction "2_2") (pintype "passive"))
    )
    (net (code "94") (name "Net-(TF-DAT1)") (class "Default")
      (node (ref "R14") (pin "1") (pinfunction "1_1") (pintype "passive"))
      (node (ref "TF") (pin "P8") (pinfunction "DAT1_P8") (pintype "bidirectional"))
    )
    (net (code "95") (name "Net-(TF-DAT2)") (class "Default")
      (node (ref "R10") (pin "1") (pinfunction "1_1") (pintype "passive"))
      (node (ref "TF") (pin "P1") (pinfunction "DAT2_P1") (pintype "bidirectional"))
    )
    (net (code "96") (name "Net-(U2-CHRG)") (class "Default")
      (node (ref "R41") (pin "1") (pinfunction "1_1") (pintype "passive"))
      (node (ref "U2") (pin "7") (pinfunction "CHRG_7") (pintype "bidirectional"))
    )
    (net (code "97") (name "Net-(U2-DONE)") (class "Default")
      (node (ref "R4") (pin "1") (pinfunction "1_1") (pintype "passive"))
      (node (ref "U2") (pin "6") (pinfunction "DONE_6") (pintype "bidirectional"))
    )
    (net (code "98") (name "Net-(U2-ISET)") (class "Default")
      (node (ref "R2") (pin "2") (pinfunction "2_2") (pintype "passive"))
      (node (ref "U2") (pin "2") (pinfunction "ISET_2") (pintype "bidirectional"))
    )
    (net (code "99") (name "Net-(U3-LNA_IN)") (class "Default")
      (node (ref "C5") (pin "2") (pinfunction "2_2") (pintype "passive"))
      (node (ref "L1") (pin "2") (pinfunction "2_2") (pintype "passive"))
      (node (ref "U3") (pin "1") (pinfunction "LNA_IN_1") (pintype "bidirectional"))
    )
    (net (code "100") (name "Net-(U3-SPICLK)") (class "Default")
      (node (ref "R18") (pin "2") (pinfunction "2_2") (pintype "passive"))
      (node (ref "U3") (pin "33") (pinfunction "SPICLK_33") (pintype "bidirectional"))
    )
    (net (code "101") (name "Net-(U3-SPID)") (class "Default")
      (node (ref "R28") (pin "2") (pinfunction "2_2") (pintype "passive"))
      (node (ref "U3") (pin "35") (pinfunction "SPID_35") (pintype "bidirectional"))
    )
    (net (code "102") (name "Net-(U3-SPIHD)") (class "Default")
      (node (ref "R25") (pin "2") (pinfunction "2_2") (pintype "passive"))
      (node (ref "U3") (pin "30") (pinfunction "SPIHD_30") (pintype "bidirectional"))
    )
    (net (code "103") (name "Net-(U3-SPIQ)") (class "Default")
      (node (ref "R16") (pin "2") (pinfunction "2_2") (pintype "passive"))
      (node (ref "U3") (pin "34") (pinfunction "SPIQ_34") (pintype "bidirectional"))
    )
    (net (code "104") (name "Net-(U3-SPIWP)") (class "Default")
      (node (ref "R23") (pin "2") (pinfunction "2_2") (pintype "passive"))
      (node (ref "U3") (pin "31") (pinfunction "SPIWP_31") (pintype "bidirectional"))
    )
    (net (code "105") (name "Net-(U3-U0TXD)") (class "Default")
      (node (ref "R12") (pin "2") (pinfunction "2_2") (pintype "passive"))
      (node (ref "U3") (pin "49") (pinfunction "U0TXD_49") (pintype "bidirectional"))
    )
    (net (code "106") (name "Net-(U3-XTAL_N)") (class "Default")
      (node (ref "C13") (pin "2") (pinfunction "2_2") (pintype "passive"))
      (node (ref "U3") (pin "53") (pinfunction "XTAL_N_53") (pintype "bidirectional"))
      (node (ref "X1") (pin "3") (pinfunction "X2_3") (pintype "bidirectional"))
    )
    (net (code "107") (name "Net-(U3-XTAL_P)") (class "Default")
      (node (ref "R34") (pin "2") (pinfunction "2_2") (pintype "passive"))
      (node (ref "U3") (pin "54") (pinfunction "XTAL_P_54") (pintype "bidirectional"))
    )
    (net (code "108") (name "Net-(U6-AD0)") (class "Default")
      (node (ref "R3") (pin "2") (pinfunction "2_2") (pintype "passive"))
      (node (ref "R36") (pin "2") (pinfunction "2_2") (pintype "passive"))
      (node (ref "U6") (pin "1") (pinfunction "AD0_1") (pintype "bidirectional"))
    )
    (net (code "109") (name "Net-(U6-AD1)") (class "Default")
      (node (ref "R42") (pin "2") (pinfunction "2_2") (pintype "passive"))
      (node (ref "R5") (pin "2") (pinfunction "2_2") (pintype "passive"))
      (node (ref "U6") (pin "2") (pinfunction "AD1_2") (pintype "bidirectional"))
    )
    (net (code "110") (name "Net-(U6-MIC1N)") (class "Default")
      (node (ref "C67") (pin "2") (pinfunction "2_2") (pintype "passive"))
      (node (ref "U6") (pin "15") (pinfunction "MIC1N_15") (pintype "bidirectional"))
    )
    (net (code "111") (name "Net-(U6-MIC1P)") (class "Default")
      (node (ref "C66") (pin "2") (pinfunction "2_2") (pintype "passive"))
      (node (ref "U6") (pin "16") (pinfunction "MIC1P_16") (pintype "bidirectional"))
    )
    (net (code "112") (name "Net-(U6-MIC2N)") (class "Default")
      (node (ref "C64") (pin "2") (pinfunction "2_2") (pintype "passive"))
      (node (ref "U6") (pin "20") (pinfunction "MIC2N_20") (pintype "bidirectional"))
    )
    (net (code "113") (name "Net-(U6-MIC2P)") (class "Default")
      (node (ref "C65") (pin "2") (pinfunction "2_2") (pintype "passive"))
      (node (ref "U6") (pin "19") (pinfunction "MIC2P_19") (pintype "bidirectional"))
    )
    (net (code "114") (name "Net-(U6-MIC3N)") (class "Default")
      (node (ref "C71") (pin "2") (pinfunction "2_2") (pintype "passive"))
      (node (ref "U6") (pin "32") (pinfunction "MIC3N_32") (pintype "bidirectional"))
    )
    (net (code "115") (name "Net-(U6-MIC3P)") (class "Default")
      (node (ref "C70") (pin "2") (pinfunction "2_2") (pintype "passive"))
      (node (ref "U6") (pin "31") (pinfunction "MIC3P_31") (pintype "bidirectional"))
    )
    (net (code "116") (name "Net-(U6-MIC4N)") (class "Default")
      (node (ref "C69") (pin "2") (pinfunction "2_2") (pintype "passive"))
      (node (ref "U6") (pin "27") (pinfunction "MIC4N_27") (pintype "bidirectional"))
    )
    (net (code "117") (name "Net-(U6-MIC4P)") (class "Default")
      (node (ref "C68") (pin "2") (pinfunction "2_2") (pintype "passive"))
      (node (ref "U6") (pin "28") (pinfunction "MIC4P_28") (pintype "bidirectional"))
    )
    (net (code "118") (name "Net-(U6-REFP12)") (class "Default")
      (node (ref "C98") (pin "1") (pinfunction "1_1") (pintype "passive"))
      (node (ref "U6") (pin "17") (pinfunction "REFP12_17") (pintype "bidirectional"))
    )
    (net (code "119") (name "Net-(U6-REFP34)") (class "Default")
      (node (ref "C59") (pin "1") (pinfunction "1_1") (pintype "passive"))
      (node (ref "U6") (pin "29") (pinfunction "REFP34_29") (pintype "bidirectional"))
    )
    (net (code "120") (name "Net-(U6-REFQ12)") (class "Default")
      (node (ref "C40") (pin "1") (pinfunction "1_1") (pintype "passive"))
      (node (ref "U6") (pin "18") (pinfunction "REFQ12_18") (pintype "bidirectional"))
    )
    (net (code "121") (name "Net-(U6-REFQ34)") (class "Default")
      (node (ref "C60") (pin "1") (pinfunction "1_1") (pintype "passive"))
      (node (ref "U6") (pin "30") (pinfunction "REFQ34_30") (pintype "bidirectional"))
    )
    (net (code "122") (name "Net-(U6-REFQM)") (class "Default")
      (node (ref "C41") (pin "1") (pinfunction "1_1") (pintype "passive"))
      (node (ref "U6") (pin "25") (pinfunction "REFQM_25") (pintype "bidirectional"))
    )
    (net (code "123") (name "Net-(U6-SOUT1)") (class "Default")
      (node (ref "R40") (pin "1") (pinfunction "1_1") (pintype "passive"))
      (node (ref "U6") (pin "11") (pinfunction "SOUT1_11") (pintype "bidirectional"))
    )
    (net (code "124") (name "Net-(U6-SOUT2)") (class "Default")
      (node (ref "R26") (pin "1") (pinfunction "1_1") (pintype "passive"))
      (node (ref "R38") (pin "1") (pinfunction "1_1") (pintype "passive"))
      (node (ref "U6") (pin "12") (pinfunction "SOUT2_12") (pintype "bidirectional"))
    )
    (net (code "125") (name "Net-(U7-INT1)") (class "Default")
      (node (ref "R39") (pin "1") (pinfunction "1_1") (pintype "passive"))
      (node (ref "U7") (pin "4") (pinfunction "INT1_4") (pintype "bidirectional"))
    )
    (net (code "126") (name "Net-(USB1-CC1)") (class "Default")
      (node (ref "R32") (pin "1") (pinfunction "1_1") (pintype "passive"))
      (node (ref "USB1") (pin "A5") (pinfunction "CC1_A5") (pintype "bidirectional"))
    )
    (net (code "127") (name "Net-(USB1-CC2)") (class "Default")
      (node (ref "R31") (pin "1") (pinfunction "1_1") (pintype "passive"))
      (node (ref "USB1") (pin "B5") (pinfunction "CC2_B5") (pintype "bidirectional"))
    )
    (net (code "128") (name "Net-(X1-X1)") (class "Default")
      (node (ref "C19") (pin "1") (pinfunction "1_1") (pintype "passive"))
      (node (ref "R34") (pin "1") (pinfunction "1_1") (pintype "passive"))
      (node (ref "X1") (pin "1") (pinfunction "X1_1") (pintype "bidirectional"))
    )
    (net (code "129") (name "V_BATT") (class "Default")
      (node (ref "BAT") (pin "+") (pinfunction "1_+") (pintype "bidirectional"))
      (node (ref "C36") (pin "1") (pinfunction "1_1") (pintype "passive"))
      (node (ref "C6") (pin "1") (pinfunction "1_1") (pintype "passive"))
      (node (ref "Q1") (pin "3") (pinfunction "D_3") (pintype "passive"))
      (node (ref "U1") (pin "2") (pinfunction "CELL_2") (pintype "input"))
      (node (ref "U1") (pin "3") (pinfunction "VDD_3") (pintype "bidirectional"))
      (node (ref "U2") (pin "5") (pinfunction "BAT_5") (pintype "bidirectional"))
    )
    (net (code "130") (name "unconnected-(J5-Pad1)") (class "Default")
      (node (ref "J5") (pin "1") (pinfunction "1_1") (pintype "bidirectional"))
    )
    (net (code "131") (name "unconnected-(J5-Pad2)") (class "Default")
      (node (ref "J5") (pin "2") (pinfunction "2_2") (pintype "bidirectional"))
    )
    (net (code "132") (name "unconnected-(J5-Pad24)") (class "Default")
      (node (ref "J5") (pin "24") (pinfunction "24_24") (pintype "bidirectional"))
    )
    (net (code "133") (name "unconnected-(P2-Pad1)") (class "Default")
      (node (ref "P2") (pin "1") (pinfunction "1_1") (pintype "bidirectional"))
    )
    (net (code "134") (name "unconnected-(P2-Pad4)") (class "Default")
      (node (ref "P2") (pin "4") (pinfunction "4_4") (pintype "bidirectional"))
    )
    (net (code "135") (name "unconnected-(P2-Pad6)") (class "Default")
      (node (ref "P2") (pin "6") (pinfunction "6_6") (pintype "bidirectional"))
    )
    (net (code "136") (name "unconnected-(P2-Pad7)") (class "Default")
      (node (ref "P2") (pin "7") (pinfunction "7_7") (pintype "bidirectional"))
    )
    (net (code "137") (name "unconnected-(TF-CD{slash}DAT3-PadP2)") (class "Default")
      (node (ref "TF") (pin "P2") (pinfunction "CD/DAT3_P2") (pintype "bidirectional"))
    )
    (net (code "138") (name "unconnected-(TF-SWITCH-PadG1)") (class "Default")
      (node (ref "TF") (pin "G1") (pinfunction "SWITCH_G1") (pintype "bidirectional"))
    )
    (net (code "139") (name "unconnected-(U1-~{ALRT}-Pad5)") (class "Default")
      (node (ref "U1") (pin "5") (pinfunction "~{ALRT}_5") (pintype "bidirectional"))
    )
    (net (code "140") (name "unconnected-(U3-GPIO33-Pad38)") (class "Default")
      (node (ref "U3") (pin "38") (pinfunction "GPIO33_38") (pintype "bidirectional"))
    )
    (net (code "141") (name "unconnected-(U3-GPIO34-Pad39)") (class "Default")
      (node (ref "U3") (pin "39") (pinfunction "GPIO34_39") (pintype "bidirectional"))
    )
    (net (code "142") (name "unconnected-(U3-GPIO35-Pad40)") (class "Default")
      (node (ref "U3") (pin "40") (pinfunction "GPIO35_40") (pintype "bidirectional"))
    )
    (net (code "143") (name "unconnected-(U3-GPIO36-Pad41)") (class "Default")
      (node (ref "U3") (pin "41") (pinfunction "GPIO36_41") (pintype "bidirectional"))
    )
    (net (code "144") (name "unconnected-(U3-GPIO37-Pad42)") (class "Default")
      (node (ref "U3") (pin "42") (pinfunction "GPIO37_42") (pintype "bidirectional"))
    )
    (net (code "145") (name "unconnected-(U5-BYP-Pad4)") (class "Default")
      (node (ref "U5") (pin "4") (pinfunction "BYP_4") (pintype "bidirectional"))
    )
    (net (code "146") (name "unconnected-(U6-DMIC_CLK-Pad14)") (class "Default")
      (node (ref "U6") (pin "14") (pinfunction "DMIC_CLK_14") (pintype "bidirectional"))
    )
    (net (code "147") (name "unconnected-(U6-INT-Pad13)") (class "Default")
      (node (ref "U6") (pin "13") (pinfunction "INT_13") (pintype "bidirectional"))
    )
    (net (code "148") (name "unconnected-(U7-CS-AUX-Pad10)") (class "Default")
      (node (ref "U7") (pin "10") (pinfunction "CS-AUX_10") (pintype "bidirectional"))
    )
    (net (code "149") (name "unconnected-(U7-INT2-Pad9)") (class "Default")
      (node (ref "U7") (pin "9") (pinfunction "INT2_9") (pintype "bidirectional"))
    )
    (net (code "150") (name "unconnected-(U7-SDO-AUX-Pad11)") (class "Default")
      (node (ref "U7") (pin "11") (pinfunction "SDO-AUX_11") (pintype "bidirectional"))
    )
    (net (code "151") (name "unconnected-(U10-BYP-Pad4)") (class "Default")
      (node (ref "U10") (pin "4") (pinfunction "BYP_4") (pintype "bidirectional"))
    )
    (net (code "152") (name "unconnected-(U13-BYP-Pad4)") (class "Default")
      (node (ref "U13") (pin "4") (pinfunction "BYP_4") (pintype "bidirectional"))
    )
    (net (code "153") (name "unconnected-(U16-BYP-Pad4)") (class "Default")
      (node (ref "U16") (pin "4") (pinfunction "BYP_4") (pintype "bidirectional"))
    )
  )
)
